# Pinscape_Pico_Expansion_Board_-_DIY_Frie.net
KiCad netlist of a schematic drawn in EAGLE
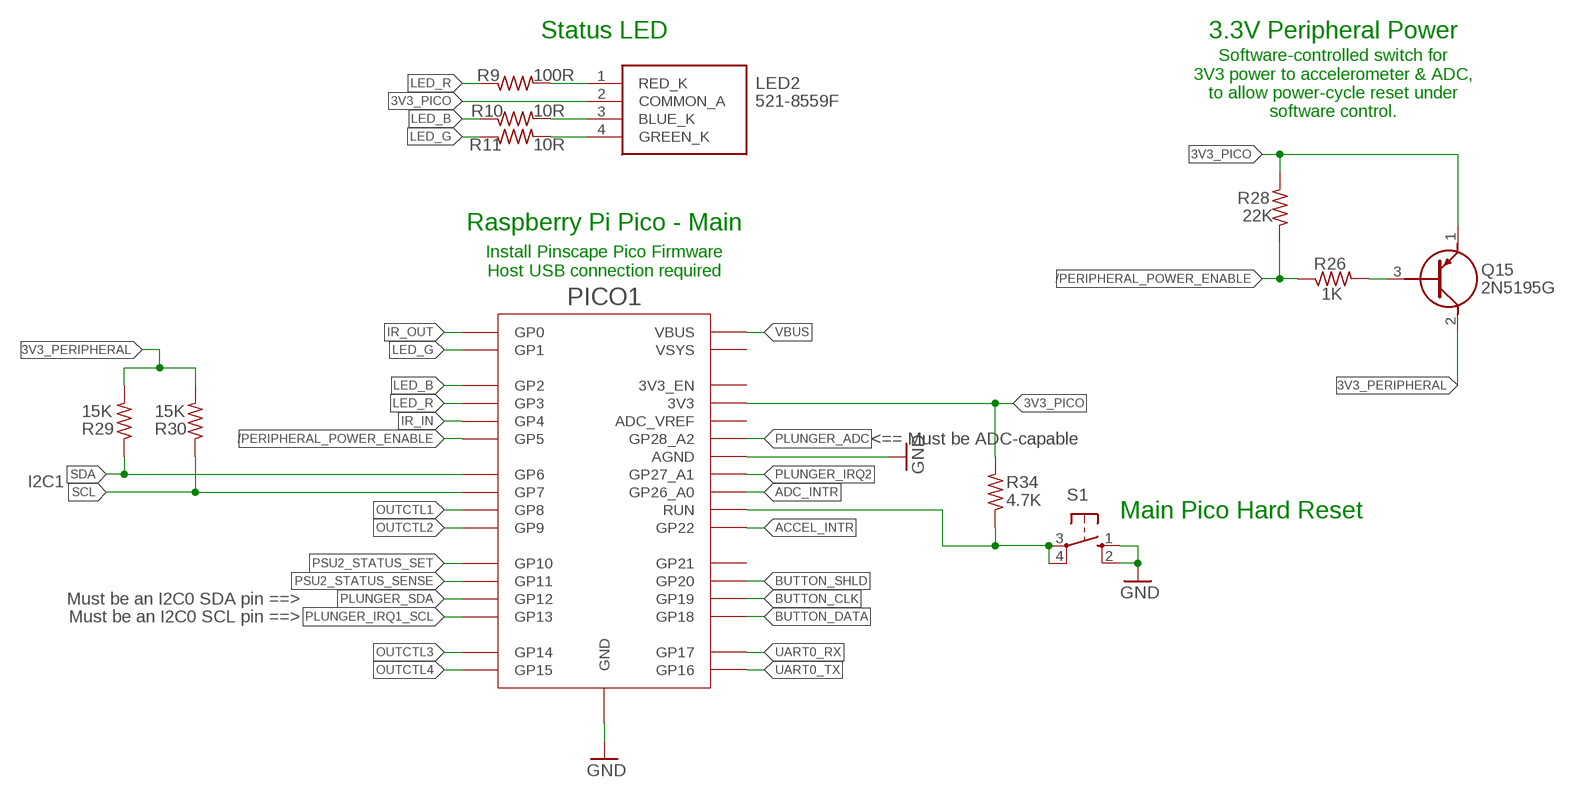
[diagram p0: schematic, sheet 1]
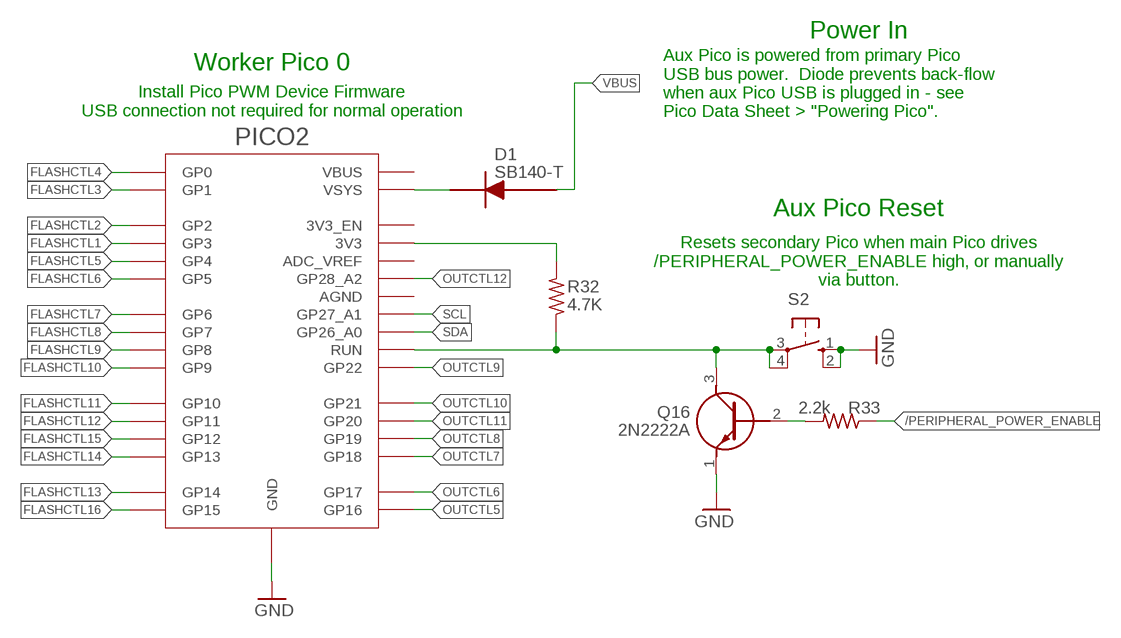
[diagram p1: schematic, sheet 2]
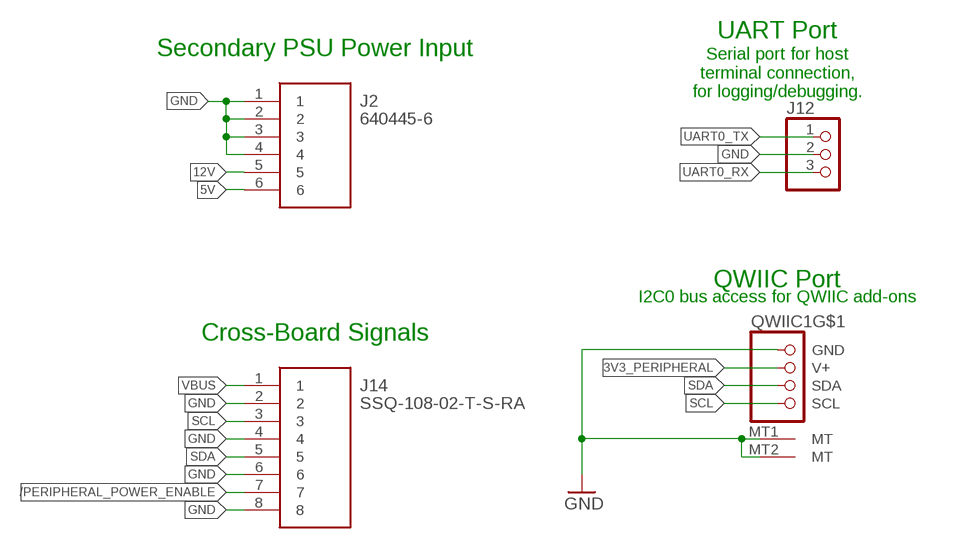
[diagram p2: schematic, sheet 3]
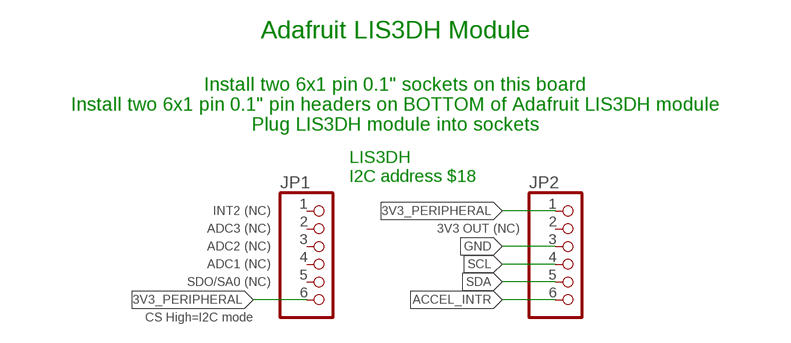
[diagram p3: schematic, sheet 4]
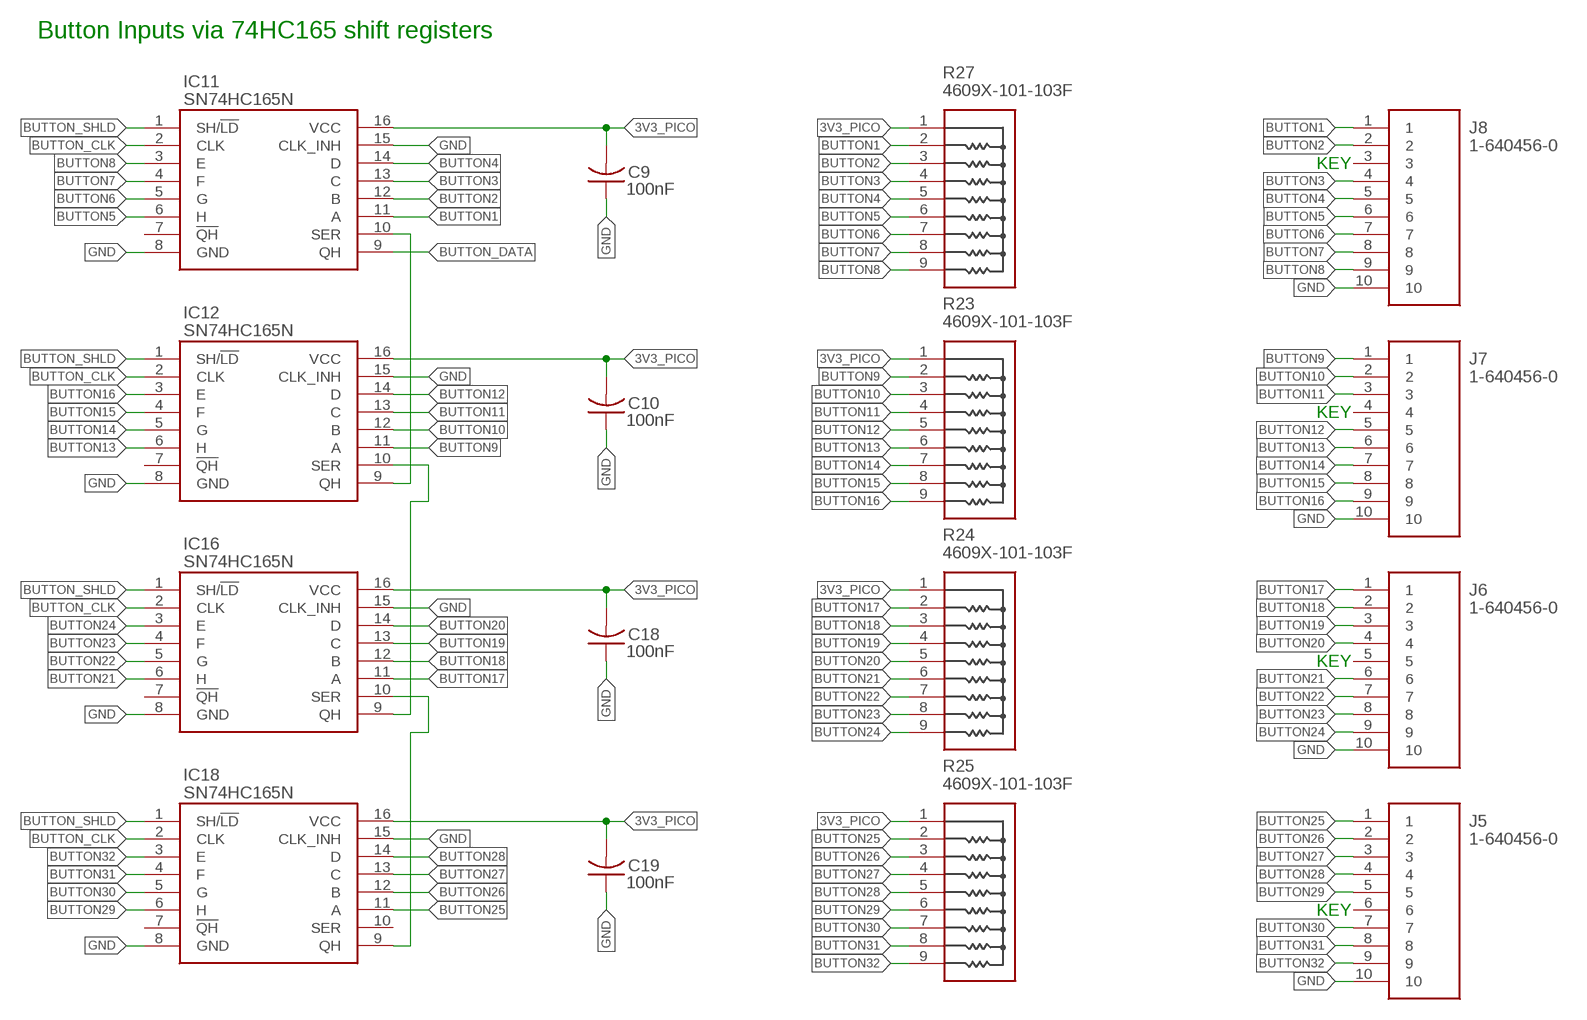
[diagram p4: schematic, sheet 5]
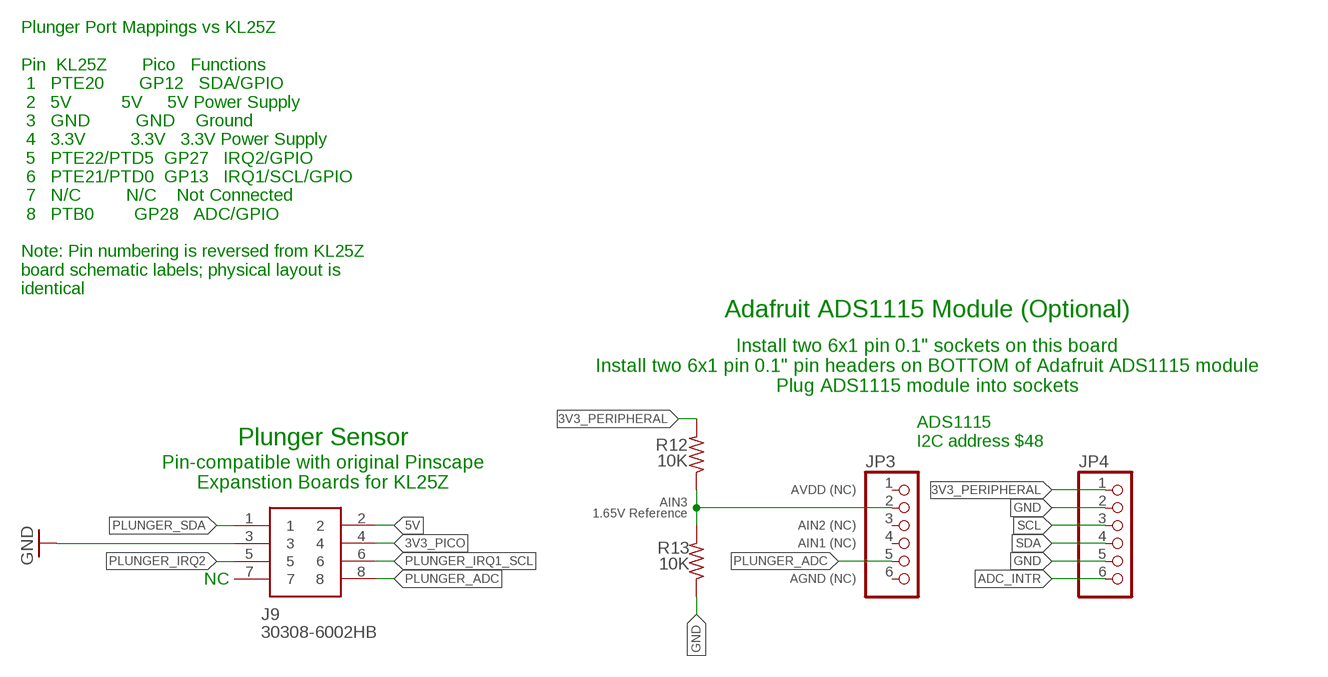
[diagram p5: schematic, sheet 6]
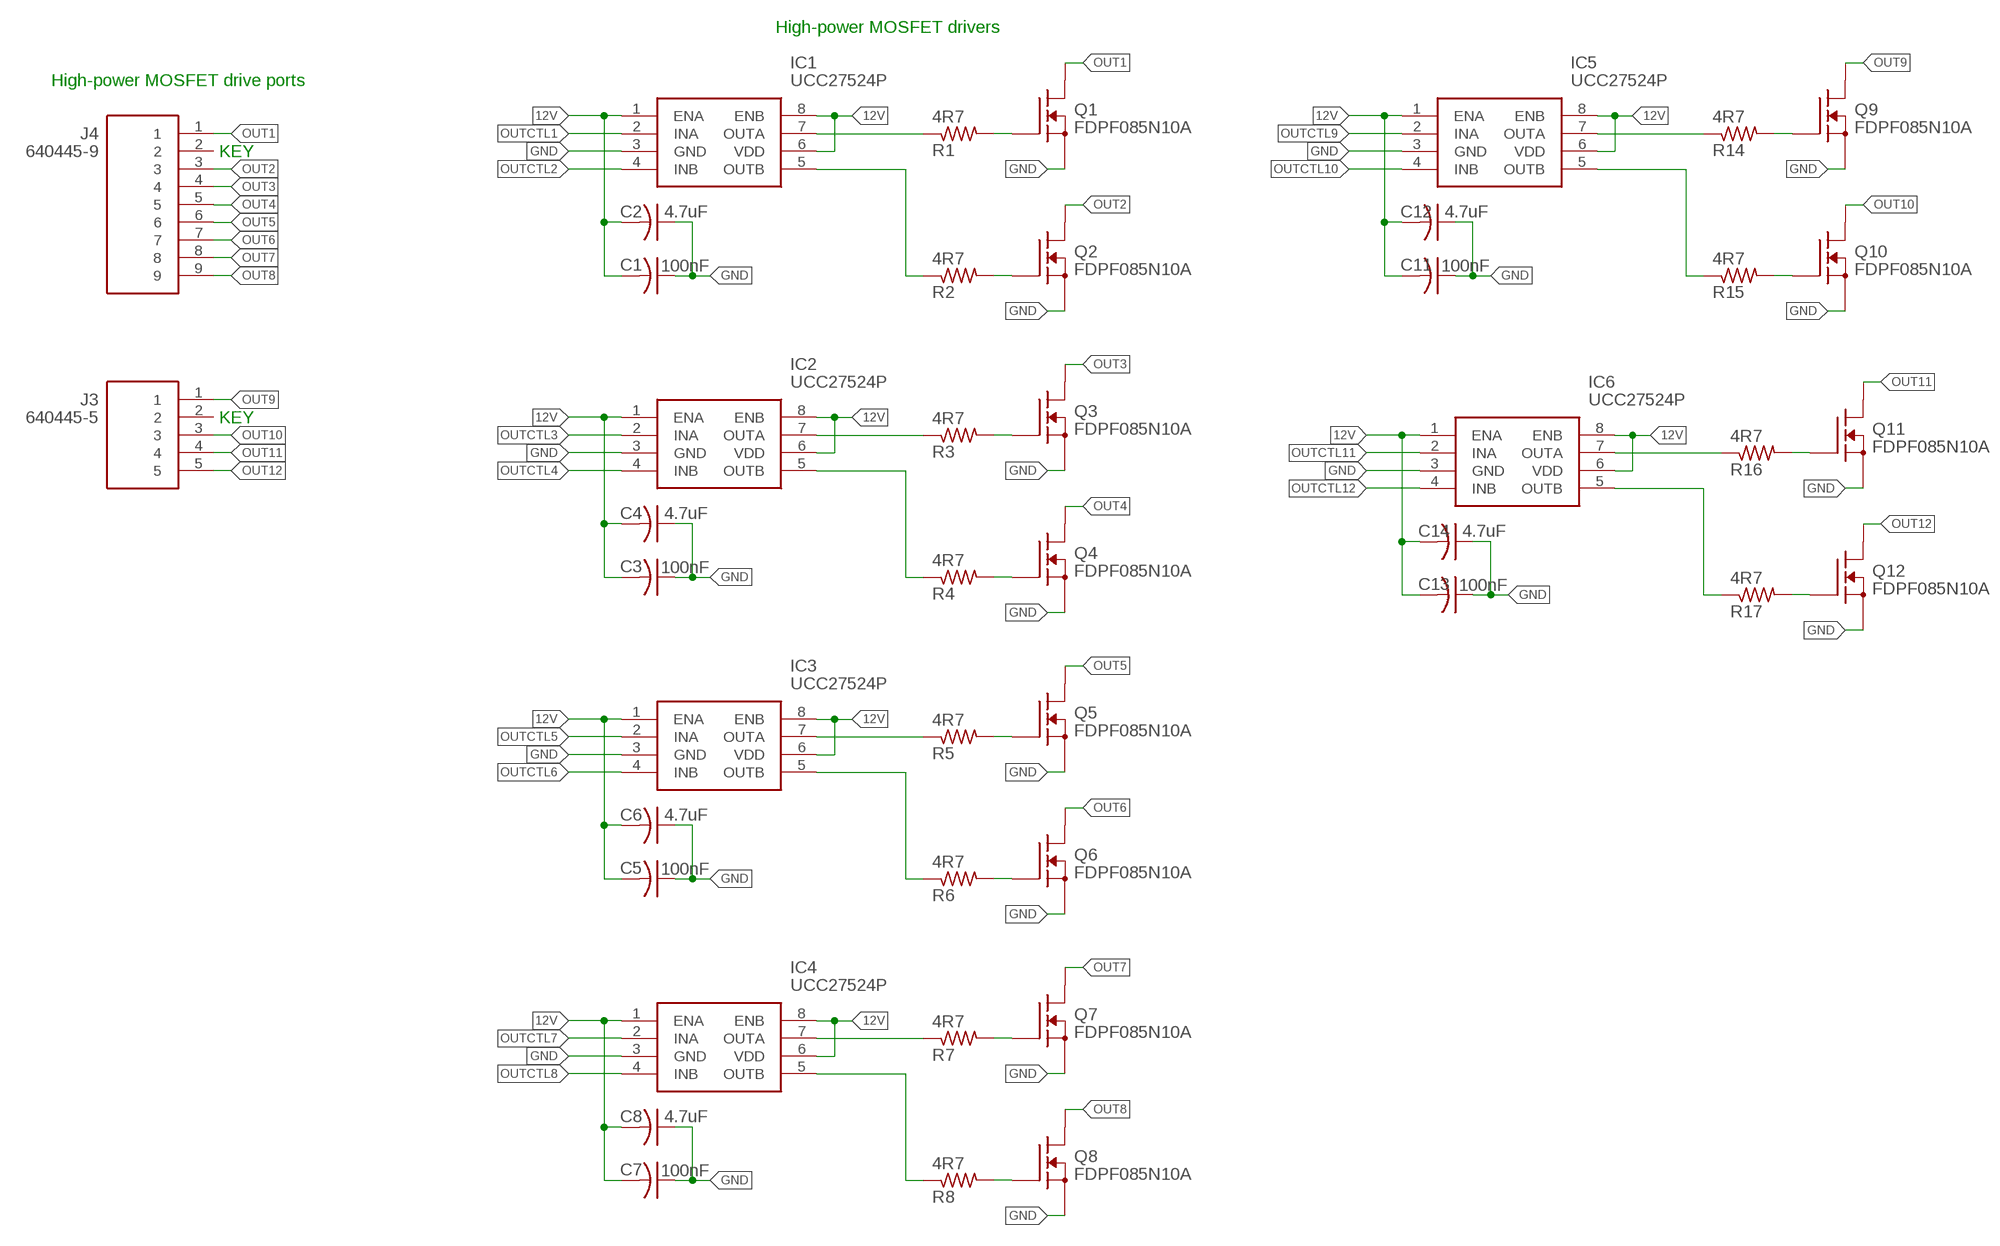
[diagram p6: schematic, sheet 7]
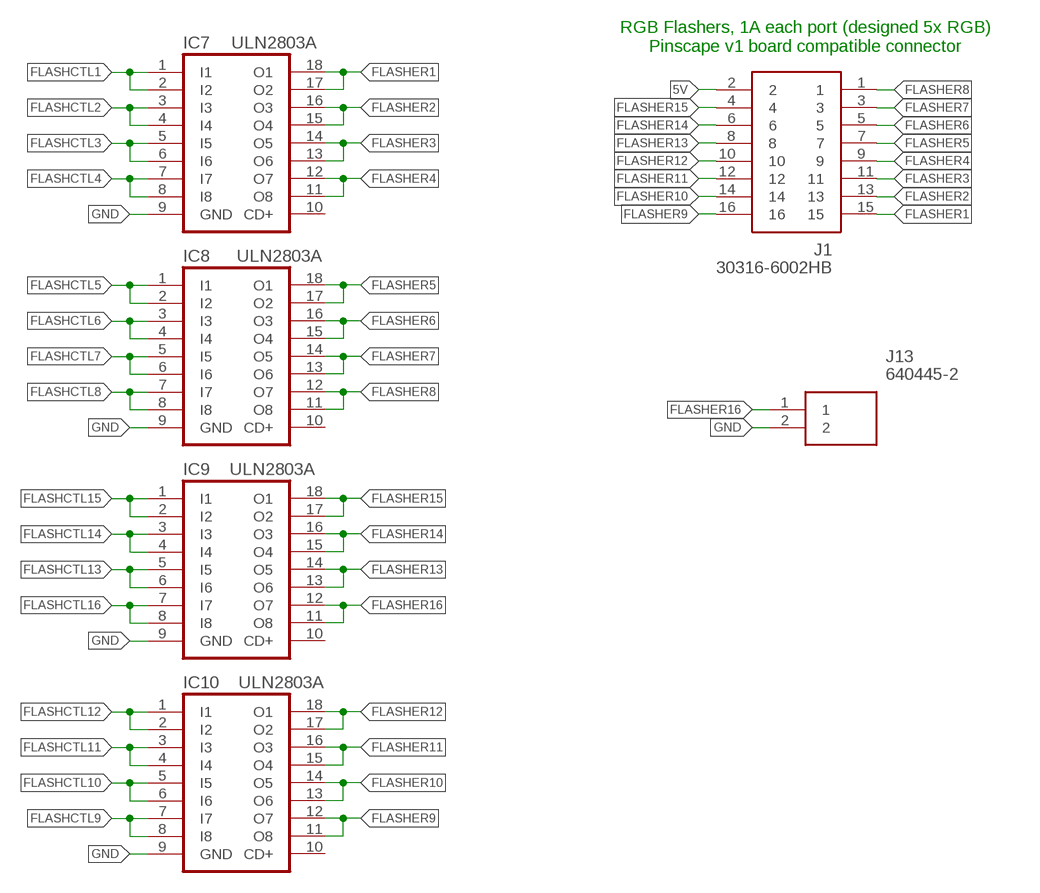
[diagram p7: schematic, sheet 8]
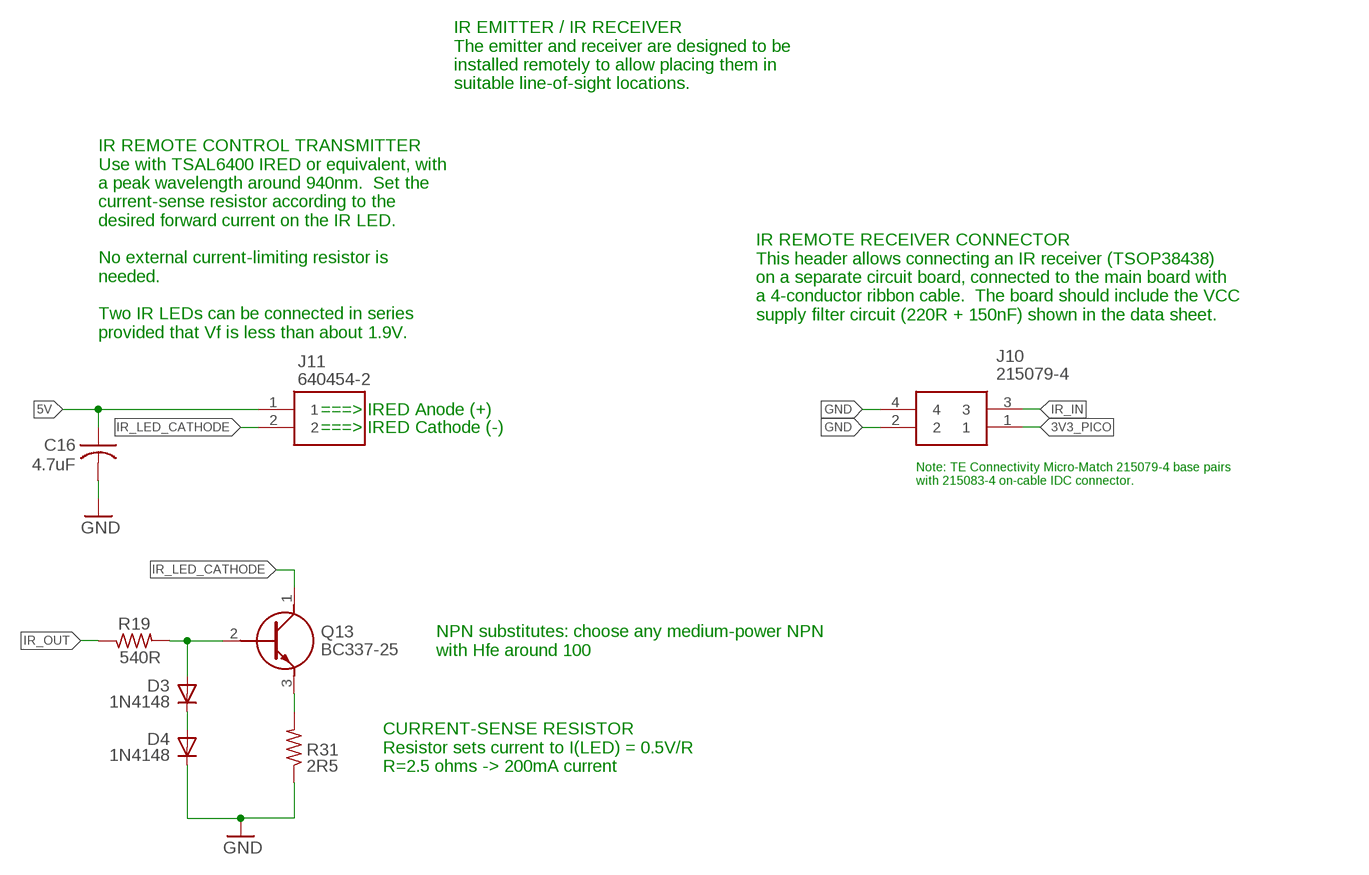
[diagram p8: schematic, sheet 9]
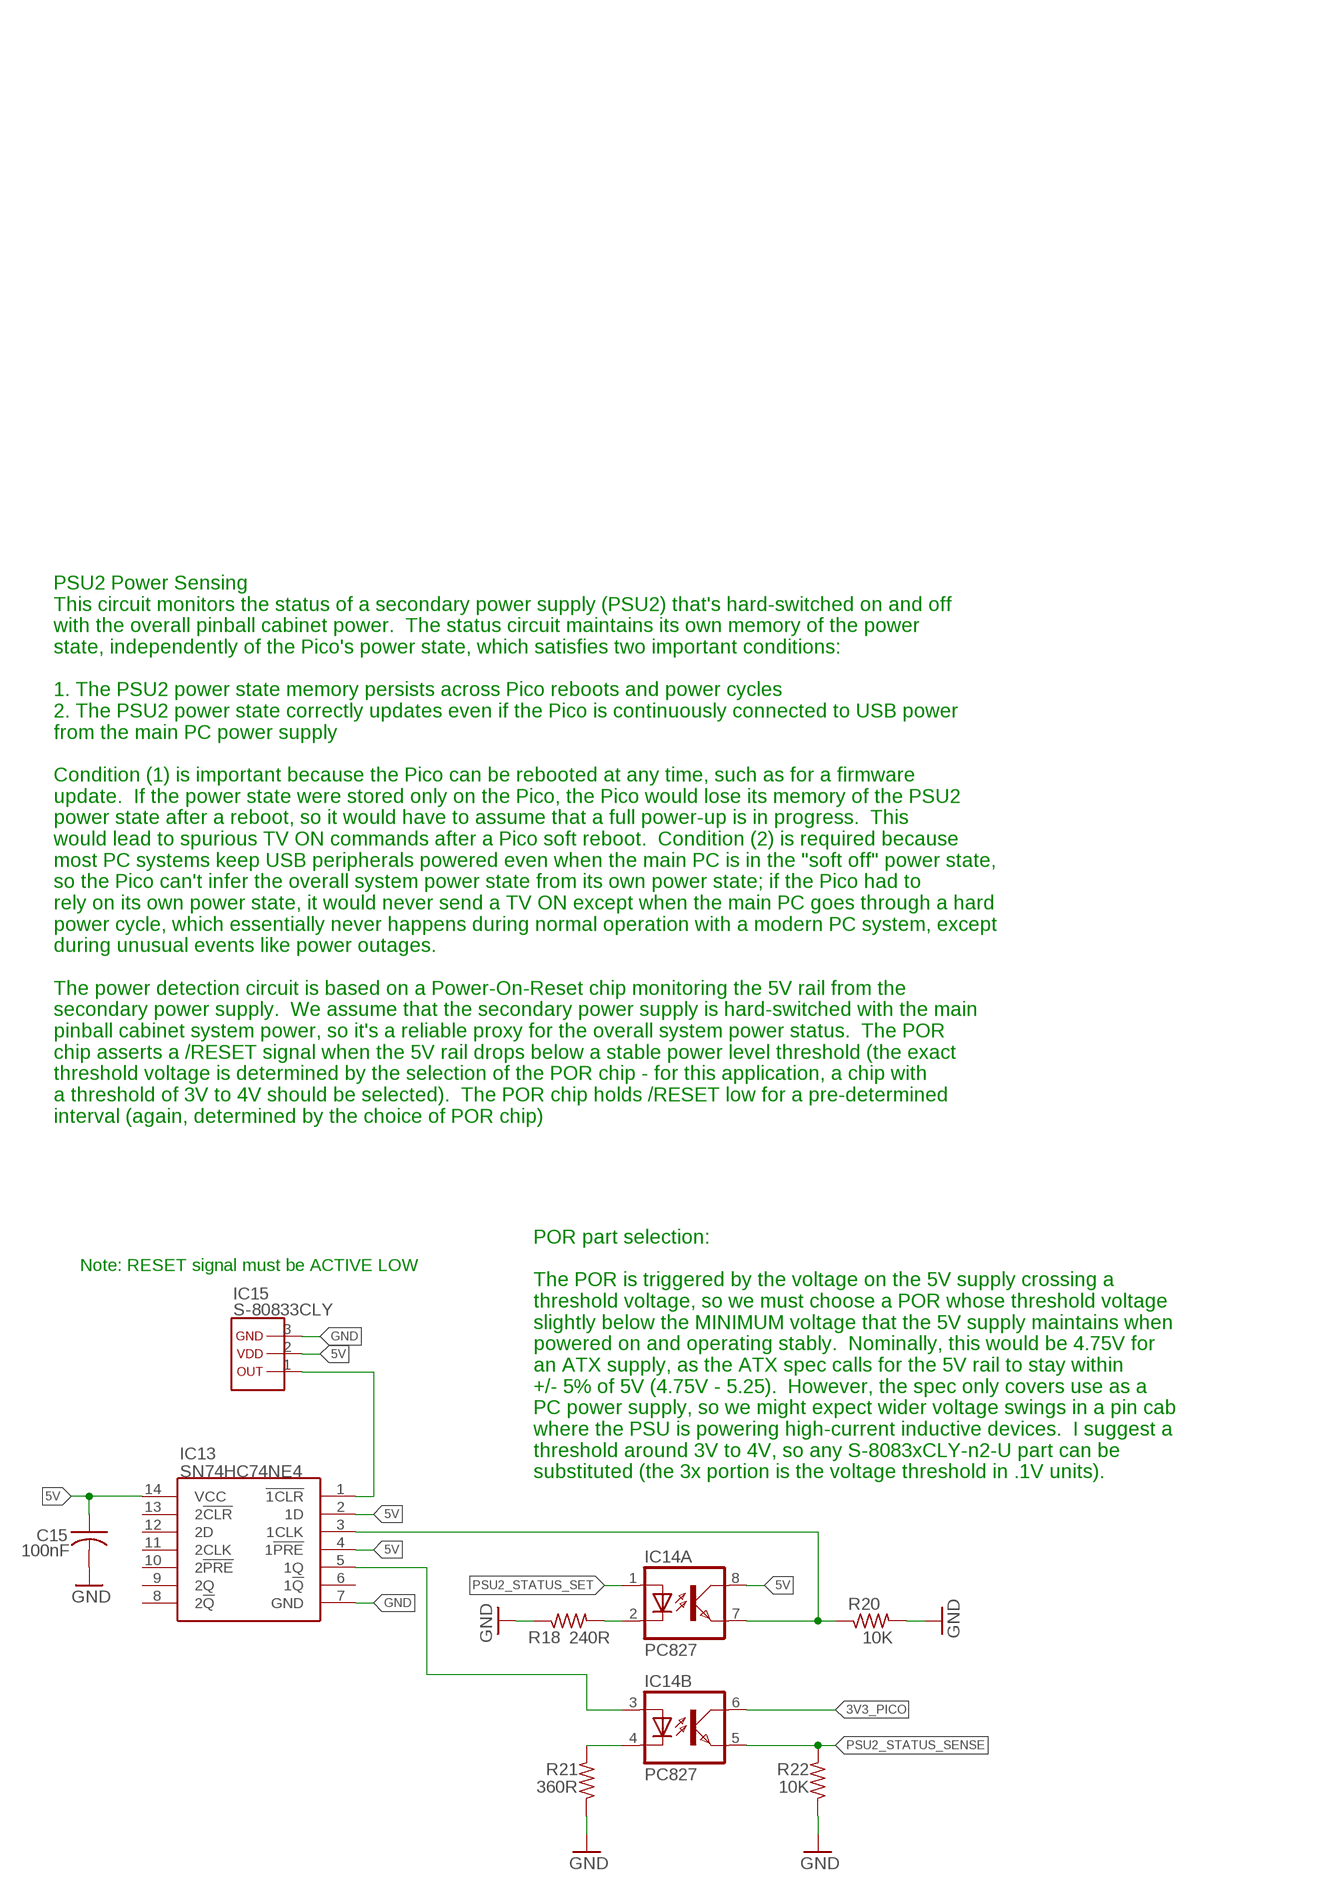
[diagram p9: schematic, sheet 10]
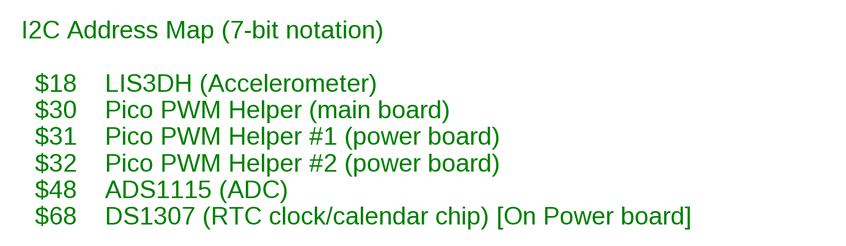
[diagram p10: schematic, sheet 11]

(export (version "E")
  (design (tool "Eeschema 10.0.6"))
  (components
    (comp (ref "C9")
      (value "100nF")
      (footprint "eagle-import:C025-024X044")
      (fields (field (name "PARTNO") "21RZ310-RC"))
      (libsource (lib "eagle-import") (part "C-US025-024X044"))
    )
    (comp (ref "C10")
      (value "100nF")
      (footprint "eagle-import:C025-024X044")
      (fields (field (name "PARTNO") "21RZ310-RC"))
      (libsource (lib "eagle-import") (part "C-US025-024X044"))
    )
    (comp (ref "C18")
      (value "100nF")
      (footprint "eagle-import:C025-024X044")
      (fields (field (name "PARTNO") "21RZ310-RC"))
      (libsource (lib "eagle-import") (part "C-US025-024X044"))
    )
    (comp (ref "C19")
      (value "100nF")
      (footprint "eagle-import:C025-024X044")
      (fields (field (name "PARTNO") "21RZ310-RC"))
      (libsource (lib "eagle-import") (part "C-US025-024X044"))
    )
    (comp (ref "IC11")
      (value "SN74HC165N")
      (footprint "eagle-import:DIP794W53P254L1930H508Q16N")
      (fields (field (name "MOUSER_PART_NUMBER") "595-SN74HC165N"))
      (libsource (lib "eagle-import") (part "SN74HC165N"))
    )
    (comp (ref "IC12")
      (value "SN74HC165N")
      (footprint "eagle-import:DIP794W53P254L1930H508Q16N")
      (fields (field (name "MOUSER_PART_NUMBER") "595-SN74HC165N"))
      (libsource (lib "eagle-import") (part "SN74HC165N"))
    )
    (comp (ref "IC16")
      (value "SN74HC165N")
      (footprint "eagle-import:DIP794W53P254L1930H508Q16N")
      (fields (field (name "MOUSER_PART_NUMBER") "595-SN74HC165N"))
      (libsource (lib "eagle-import") (part "SN74HC165N"))
    )
    (comp (ref "IC18")
      (value "SN74HC165N")
      (footprint "eagle-import:DIP794W53P254L1930H508Q16N")
      (fields (field (name "MOUSER_PART_NUMBER") "595-SN74HC165N"))
      (libsource (lib "eagle-import") (part "SN74HC165N"))
    )
    (comp (ref "J5")
      (value "1-640456-0")
      (footprint "eagle-import:SHDR10W66P0X254_1X10_2540X572X")
      (fields (field (name "MOUSER_PART_NUMBER") "571-16404560"))
      (libsource (lib "eagle-import") (part "1-640456-0"))
    )
    (comp (ref "J6")
      (value "1-640456-0")
      (footprint "eagle-import:SHDR10W66P0X254_1X10_2540X572X")
      (fields (field (name "MOUSER_PART_NUMBER") "571-16404560"))
      (libsource (lib "eagle-import") (part "1-640456-0"))
    )
    (comp (ref "J7")
      (value "1-640456-0")
      (footprint "eagle-import:SHDR10W66P0X254_1X10_2540X572X")
      (fields (field (name "MOUSER_PART_NUMBER") "571-16404560"))
      (libsource (lib "eagle-import") (part "1-640456-0"))
    )
    (comp (ref "J8")
      (value "1-640456-0")
      (footprint "eagle-import:SHDR10W66P0X254_1X10_2540X572X")
      (fields (field (name "MOUSER_PART_NUMBER") "571-16404560"))
      (libsource (lib "eagle-import") (part "1-640456-0"))
    )
    (comp (ref "R23")
      (value "4609X-101-103F")
      (footprint "eagle-import:4609X")
      (fields
        (field (name "MANUFACTURER_PART_NUMBER") "4609X-101-122LF")
        (field (name "MOUSER_PART_NUMBER") "652-4609X-1LF-1.2K")
      )
      (libsource (lib "eagle-import") (part "4609X-101-122LF"))
    )
    (comp (ref "R24")
      (value "4609X-101-103F")
      (footprint "eagle-import:4609X")
      (fields
        (field (name "MANUFACTURER_PART_NUMBER") "4609X-101-122LF")
        (field (name "MOUSER_PART_NUMBER") "652-4609X-1LF-1.2K")
      )
      (libsource (lib "eagle-import") (part "4609X-101-122LF"))
    )
    (comp (ref "R25")
      (value "4609X-101-103F")
      (footprint "eagle-import:4609X")
      (fields
        (field (name "MANUFACTURER_PART_NUMBER") "4609X-101-122LF")
        (field (name "MOUSER_PART_NUMBER") "652-4609X-1LF-1.2K")
      )
      (libsource (lib "eagle-import") (part "4609X-101-122LF"))
    )
    (comp (ref "R27")
      (value "4609X-101-103F")
      (footprint "eagle-import:4609X")
      (fields
        (field (name "MANUFACTURER_PART_NUMBER") "4609X-101-122LF")
        (field (name "MOUSER_PART_NUMBER") "652-4609X-1LF-1.2K")
      )
      (libsource (lib "eagle-import") (part "4609X-101-122LF"))
    )
    (comp (ref "JP1")
      (value "PINHD-1X6")
      (footprint "eagle-import:1X06")
      (libsource (lib "eagle-import") (part "PINHD-1X6"))
    )
    (comp (ref "JP2")
      (value "PINHD-1X6")
      (footprint "eagle-import:1X06")
      (libsource (lib "eagle-import") (part "PINHD-1X6"))
    )
    (comp (ref "J2")
      (value "640445-6")
      (footprint "eagle-import:SHDR6W183P0X396_1X6_2377X762X1")
      (fields (field (name "MOUSER_PART_NUMBER") "571-6404456"))
      (libsource (lib "eagle-import") (part "640445-6"))
    )
    (comp (ref "J12")
      (value "PINHD-1X3")
      (footprint "eagle-import:1X03")
      (libsource (lib "eagle-import") (part "PINHD-1X3"))
    )
    (comp (ref "J14")
      (value "SSQ-108-02-T-S-RA")
      (footprint "eagle-import:RHDRRA8W64P254_1X8_2083X851X24")
      (fields (field (name "MOUSER_PART_NUMBER") "200-SSQ10802TSRA"))
      (libsource (lib "eagle-import") (part "SSQ-108-02-T-S-RA"))
    )
    (comp (ref "QWIIC1")
      (value "QWIIC")
      (footprint "eagle-import:JST_SH4")
      (libsource (lib "eagle-import") (part "STEMMA_I2C_QT"))
    )
    (comp (ref "C16")
      (value "4.7uF")
      (footprint "eagle-import:C025-024X044")
      (fields (field (name "PARTNO") "810-FG14X5R1H475KRT0"))
      (libsource (lib "eagle-import") (part "C-US025-024X044"))
    )
    (comp (ref "D3")
      (value "1N4148")
      (footprint "eagle-import:DO35-7")
      (libsource (lib "eagle-import") (part "1N4148DO35-7"))
    )
    (comp (ref "D4")
      (value "1N4148")
      (footprint "eagle-import:DO35-7")
      (libsource (lib "eagle-import") (part "1N4148DO35-7"))
    )
    (comp (ref "J10")
      (value "215079-4")
      (footprint "eagle-import:2150794")
      (fields (field (name "MOUSER_PART_NUMBER") "571-215079-4"))
      (libsource (lib "eagle-import") (part "215079-4"))
    )
    (comp (ref "J11")
      (value "640454-2")
      (footprint "eagle-import:HDRV2W66P0X254_1X2_762X572X100")
      (fields (field (name "MOUSER_PART_NUMBER") "571-640454-2"))
      (libsource (lib "eagle-import") (part "640454-2"))
    )
    (comp (ref "Q13")
      (value "BC337-25")
      (footprint "eagle-import:BC33725")
      (fields (field (name "MOUSER_PART_NUMBER") "637-BC337-25"))
      (libsource (lib "eagle-import") (part "BC337-25"))
    )
    (comp (ref "R19")
      (value "540R")
      (footprint "eagle-import:0204_7")
      (fields (field (name "PARTNO") "660-MFS1/4DCT52R47R0"))
      (libsource (lib "eagle-import") (part "R-US_0204/7"))
    )
    (comp (ref "R31")
      (value "2R5")
      (footprint "eagle-import:0204_7")
      (fields (field (name "PARTNO") "660-MFS1/4DCT52R47R0"))
      (libsource (lib "eagle-import") (part "R-US_0204/7"))
    )
    (comp (ref "D1")
      (value "SB140-T")
      (footprint "eagle-import:DIOAD1408W86L464D236")
      (fields (field (name "MOUSER_PART_NUMBER") "621-SB140-T"))
      (libsource (lib "eagle-import") (part "SB140-T"))
    )
    (comp (ref "PICO2")
      (value "RPI_PICO_NO_DEBUG")
      (footprint "eagle-import:RPI_PICO_TH_NO_DEBUG")
      (libsource (lib "eagle-import") (part "RPI_PICO_NO_DEBUG"))
    )
    (comp (ref "Q16")
      (value "2N2222A")
      (footprint "eagle-import:2N2222A")
      (fields (field (name "MOUSER_PART_NUMBER") "637-2N2222A"))
      (libsource (lib "eagle-import") (part "2N2222A"))
    )
    (comp (ref "R32")
      (value "4.7K")
      (footprint "eagle-import:0204_7")
      (fields (field (name "PARTNO") "660-MFS1/4DCT52R47R0"))
      (libsource (lib "eagle-import") (part "R-US_0204/7"))
    )
    (comp (ref "R33")
      (value "2.2k")
      (footprint "eagle-import:0204_7")
      (fields (field (name "PARTNO") "660-MFS1/4DCT52R47R0"))
      (libsource (lib "eagle-import") (part "R-US_0204/7"))
    )
    (comp (ref "S2")
      (value "10-XX")
      (footprint "eagle-import:B3F-10XX")
      (fields (field (name "MPN") "B3F-1000"))
      (libsource (lib "eagle-import") (part "10-XX"))
    )
    (comp (ref "C15")
      (value "100nF")
      (footprint "eagle-import:C025-024X044")
      (fields (field (name "PARTNO") "21RZ310-RC"))
      (libsource (lib "eagle-import") (part "C-US025-024X044"))
    )
    (comp (ref "IC13")
      (value "SN74HC74NE4")
      (footprint "eagle-import:DIP794W53P254L1930H508Q14N")
      (fields (field (name "MOUSER_PART_NUMBER") "595-SN74HC74NE4"))
      (libsource (lib "eagle-import") (part "SN74HC74NE4"))
    )
    (comp (ref "IC14")
      (value "PC827")
      (footprint "eagle-import:DIL08")
      (libsource (lib "eagle-import") (part "PC827"))
    )
    (comp (ref "IC15")
      (value "S-80833CLY")
      (footprint "eagle-import:TO-92_(TO-226)")
      (libsource (lib "eagle-import") (part "S-80833CLY-B2-UTO92"))
    )
    (comp (ref "R18")
      (value "240R")
      (footprint "eagle-import:0204_7")
      (fields (field (name "PARTNO") "660-MFS1/4DCT52R47R0"))
      (libsource (lib "eagle-import") (part "R-US_0204/7"))
    )
    (comp (ref "R20")
      (value "10K")
      (footprint "eagle-import:0204_7")
      (fields (field (name "PARTNO") "660-MFS1/4DCT52R47R0"))
      (libsource (lib "eagle-import") (part "R-US_0204/7"))
    )
    (comp (ref "R21")
      (value "360R")
      (footprint "eagle-import:0204_7")
      (fields (field (name "PARTNO") "660-MFS1/4DCT52R47R0"))
      (libsource (lib "eagle-import") (part "R-US_0204/7"))
    )
    (comp (ref "R22")
      (value "10K")
      (footprint "eagle-import:0204_7")
      (fields (field (name "PARTNO") "660-MFS1/4DCT52R47R0"))
      (libsource (lib "eagle-import") (part "R-US_0204/7"))
    )
    (comp (ref "LED2")
      (value "521-8559F")
      (footprint "eagle-import:5218559F")
      (fields (field (name "MOUSER_PART_NUMBER") "645-5218559F"))
      (libsource (lib "eagle-import") (part "521-8559F"))
    )
    (comp (ref "PICO1")
      (value "RPI_PICO_NO_DEBUG")
      (footprint "eagle-import:RPI_PICO_TH_NO_DEBUG")
      (libsource (lib "eagle-import") (part "RPI_PICO_NO_DEBUG"))
    )
    (comp (ref "Q15")
      (value "2N5195G")
      (footprint "eagle-import:TO229P300X760X1364-3P")
      (fields (field (name "MOUSER_PART_NUMBER") "863-2N5195G"))
      (libsource (lib "eagle-import") (part "2N5195G"))
    )
    (comp (ref "R9")
      (value "100R")
      (footprint "eagle-import:0204_7")
      (fields (field (name "PARTNO") "660-MFS1/4DCT52R47R0"))
      (libsource (lib "eagle-import") (part "R-US_0204/7"))
    )
    (comp (ref "R10")
      (value "10R")
      (footprint "eagle-import:0204_7")
      (fields (field (name "PARTNO") "660-MFS1/4DCT52R47R0"))
      (libsource (lib "eagle-import") (part "R-US_0204/7"))
    )
    (comp (ref "R11")
      (value "10R")
      (footprint "eagle-import:0204_7")
      (fields (field (name "PARTNO") "660-MFS1/4DCT52R47R0"))
      (libsource (lib "eagle-import") (part "R-US_0204/7"))
    )
    (comp (ref "R26")
      (value "1K")
      (footprint "eagle-import:0204_7")
      (fields (field (name "PARTNO") "660-MFS1/4DCT52R47R0"))
      (libsource (lib "eagle-import") (part "R-US_0204/7"))
    )
    (comp (ref "R28")
      (value "22K")
      (footprint "eagle-import:0204_7")
      (fields (field (name "PARTNO") "660-MFS1/4DCT52R47R0"))
      (libsource (lib "eagle-import") (part "R-US_0204/7"))
    )
    (comp (ref "R29")
      (value "15K")
      (footprint "eagle-import:0204_7")
      (fields (field (name "PARTNO") "660-MFS1/4DCT52R47R0"))
      (libsource (lib "eagle-import") (part "R-US_0204/7"))
    )
    (comp (ref "R30")
      (value "15K")
      (footprint "eagle-import:0204_7")
      (fields (field (name "PARTNO") "660-MFS1/4DCT52R47R0"))
      (libsource (lib "eagle-import") (part "R-US_0204/7"))
    )
    (comp (ref "R34")
      (value "4.7K")
      (footprint "eagle-import:0204_7")
      (fields (field (name "PARTNO") "660-MFS1/4DCT52R47R0"))
      (libsource (lib "eagle-import") (part "R-US_0204/7"))
    )
    (comp (ref "S1")
      (value "10-XX")
      (footprint "eagle-import:B3F-10XX")
      (fields (field (name "MPN") "B3F-1000"))
      (libsource (lib "eagle-import") (part "10-XX"))
    )
    (comp (ref "IC7")
      (value "ULN2803A")
      (footprint "eagle-import:DIL18")
      (libsource (lib "eagle-import") (part "ULN2803A"))
    )
    (comp (ref "IC8")
      (value "ULN2803A")
      (footprint "eagle-import:DIL18")
      (libsource (lib "eagle-import") (part "ULN2803A"))
    )
    (comp (ref "IC9")
      (value "ULN2803A")
      (footprint "eagle-import:DIL18")
      (libsource (lib "eagle-import") (part "ULN2803A"))
    )
    (comp (ref "IC10")
      (value "ULN2803A")
      (footprint "eagle-import:DIL18")
      (libsource (lib "eagle-import") (part "ULN2803A"))
    )
    (comp (ref "J1")
      (value "30316-6002HB")
      (footprint "eagle-import:3M-30316-6002HB")
      (fields (field (name "MOUSER_PART_NUMBER") "517-30316-6002"))
      (libsource (lib "eagle-import") (part "30316-6002HB"))
    )
    (comp (ref "J13")
      (value "640445-2")
      (footprint "eagle-import:SHDR2W117P0X396_1X2_792X762X11")
      (fields (field (name "MOUSER_PART_NUMBER") "5716404452"))
      (libsource (lib "eagle-import") (part "640445-2"))
    )
    (comp (ref "J9")
      (value "30308-6002HB")
      (footprint "eagle-import:SHDR8W69P254_2X4_1780X878X955P")
      (libsource (lib "eagle-import") (part "30308-6002HB"))
    )
    (comp (ref "JP3")
      (value "PINHD-1X6")
      (footprint "eagle-import:1X06")
      (libsource (lib "eagle-import") (part "PINHD-1X6"))
    )
    (comp (ref "JP4")
      (value "PINHD-1X6")
      (footprint "eagle-import:1X06")
      (libsource (lib "eagle-import") (part "PINHD-1X6"))
    )
    (comp (ref "R12")
      (value "10K")
      (footprint "eagle-import:0204_7")
      (fields (field (name "PARTNO") "660-MFS1/4DCT52R47R0"))
      (libsource (lib "eagle-import") (part "R-US_0204/7"))
    )
    (comp (ref "R13")
      (value "10K")
      (footprint "eagle-import:0204_7")
      (fields (field (name "PARTNO") "660-MFS1/4DCT52R47R0"))
      (libsource (lib "eagle-import") (part "R-US_0204/7"))
    )
    (comp (ref "C1")
      (value "100nF")
      (footprint "eagle-import:C025-024X044")
      (fields (field (name "PARTNO") "21RZ310-RC"))
      (libsource (lib "eagle-import") (part "C-US025-024X044"))
    )
    (comp (ref "C2")
      (value "4.7uF")
      (footprint "eagle-import:C025-024X044")
      (fields (field (name "PARTNO") "810-FG14X5R1H475KRT0"))
      (libsource (lib "eagle-import") (part "C-US025-024X044"))
    )
    (comp (ref "C3")
      (value "100nF")
      (footprint "eagle-import:C025-024X044")
      (fields (field (name "PARTNO") "21RZ310-RC"))
      (libsource (lib "eagle-import") (part "C-US025-024X044"))
    )
    (comp (ref "C4")
      (value "4.7uF")
      (footprint "eagle-import:C025-024X044")
      (fields (field (name "PARTNO") "810-FG14X5R1H475KRT0"))
      (libsource (lib "eagle-import") (part "C-US025-024X044"))
    )
    (comp (ref "C5")
      (value "100nF")
      (footprint "eagle-import:C025-024X044")
      (fields (field (name "PARTNO") "21RZ310-RC"))
      (libsource (lib "eagle-import") (part "C-US025-024X044"))
    )
    (comp (ref "C6")
      (value "4.7uF")
      (footprint "eagle-import:C025-024X044")
      (fields (field (name "PARTNO") "810-FG14X5R1H475KRT0"))
      (libsource (lib "eagle-import") (part "C-US025-024X044"))
    )
    (comp (ref "C7")
      (value "100nF")
      (footprint "eagle-import:C025-024X044")
      (fields (field (name "PARTNO") "21RZ310-RC"))
      (libsource (lib "eagle-import") (part "C-US025-024X044"))
    )
    (comp (ref "C8")
      (value "4.7uF")
      (footprint "eagle-import:C025-024X044")
      (fields (field (name "PARTNO") "810-FG14X5R1H475KRT0"))
      (libsource (lib "eagle-import") (part "C-US025-024X044"))
    )
    (comp (ref "C11")
      (value "100nF")
      (footprint "eagle-import:C025-024X044")
      (fields (field (name "PARTNO") "21RZ310-RC"))
      (libsource (lib "eagle-import") (part "C-US025-024X044"))
    )
    (comp (ref "C12")
      (value "4.7uF")
      (footprint "eagle-import:C025-024X044")
      (fields (field (name "PARTNO") "810-FG14X5R1H475KRT0"))
      (libsource (lib "eagle-import") (part "C-US025-024X044"))
    )
    (comp (ref "C13")
      (value "100nF")
      (footprint "eagle-import:C025-024X044")
      (fields (field (name "PARTNO") "21RZ310-RC"))
      (libsource (lib "eagle-import") (part "C-US025-024X044"))
    )
    (comp (ref "C14")
      (value "4.7uF")
      (footprint "eagle-import:C025-024X044")
      (fields (field (name "PARTNO") "810-FG14X5R1H475KRT0"))
      (libsource (lib "eagle-import") (part "C-US025-024X044"))
    )
    (comp (ref "IC1")
      (value "UCC27524P")
      (footprint "eagle-import:DIP794W53P254L959H508Q8N")
      (fields (field (name "MOUSER_PART_NUMBER") "595-UCC27524P"))
      (libsource (lib "eagle-import") (part "UCC27524P"))
    )
    (comp (ref "IC2")
      (value "UCC27524P")
      (footprint "eagle-import:DIP794W53P254L959H508Q8N")
      (fields (field (name "MOUSER_PART_NUMBER") "595-UCC27524P"))
      (libsource (lib "eagle-import") (part "UCC27524P"))
    )
    (comp (ref "IC3")
      (value "UCC27524P")
      (footprint "eagle-import:DIP794W53P254L959H508Q8N")
      (fields (field (name "MOUSER_PART_NUMBER") "595-UCC27524P"))
      (libsource (lib "eagle-import") (part "UCC27524P"))
    )
    (comp (ref "IC4")
      (value "UCC27524P")
      (footprint "eagle-import:DIP794W53P254L959H508Q8N")
      (fields (field (name "MOUSER_PART_NUMBER") "595-UCC27524P"))
      (libsource (lib "eagle-import") (part "UCC27524P"))
    )
    (comp (ref "IC5")
      (value "UCC27524P")
      (footprint "eagle-import:DIP794W53P254L959H508Q8N")
      (fields (field (name "MOUSER_PART_NUMBER") "595-UCC27524P"))
      (libsource (lib "eagle-import") (part "UCC27524P"))
    )
    (comp (ref "IC6")
      (value "UCC27524P")
      (footprint "eagle-import:DIP794W53P254L959H508Q8N")
      (fields (field (name "MOUSER_PART_NUMBER") "595-UCC27524P"))
      (libsource (lib "eagle-import") (part "UCC27524P"))
    )
    (comp (ref "J3")
      (value "640445-5")
      (footprint "eagle-import:HDRV5W117P0X396_1X5_1981X762X1")
      (fields (field (name "MOUSER_PART_NUMBER") "571-640445-5"))
      (libsource (lib "eagle-import") (part "640445-5"))
    )
    (comp (ref "J4")
      (value "640445-9")
      (footprint "eagle-import:SHDR9W117P0X396_1X9_3566X762X1")
      (fields (field (name "MOUSER_PART_NUMBER") "571-6404459"))
      (libsource (lib "eagle-import") (part "640445-9"))
    )
    (comp (ref "Q1")
      (value "FDPF085N10A")
      (footprint "eagle-import:TO220BV")
      (fields (field (name "PARTNO") "FDPF085N10A"))
      (libsource (lib "eagle-import") (part "BUK7575-55A"))
    )
    (comp (ref "Q2")
      (value "FDPF085N10A")
      (footprint "eagle-import:TO220BV")
      (fields (field (name "PARTNO") "FDPF085N10A"))
      (libsource (lib "eagle-import") (part "BUK7575-55A"))
    )
    (comp (ref "Q3")
      (value "FDPF085N10A")
      (footprint "eagle-import:TO220BV")
      (fields (field (name "PARTNO") "FDPF085N10A"))
      (libsource (lib "eagle-import") (part "BUK7575-55A"))
    )
    (comp (ref "Q4")
      (value "FDPF085N10A")
      (footprint "eagle-import:TO220BV")
      (fields (field (name "PARTNO") "FDPF085N10A"))
      (libsource (lib "eagle-import") (part "BUK7575-55A"))
    )
    (comp (ref "Q5")
      (value "FDPF085N10A")
      (footprint "eagle-import:TO220BV")
      (fields (field (name "PARTNO") "FDPF085N10A"))
      (libsource (lib "eagle-import") (part "BUK7575-55A"))
    )
    (comp (ref "Q6")
      (value "FDPF085N10A")
      (footprint "eagle-import:TO220BV")
      (fields (field (name "PARTNO") "FDPF085N10A"))
      (libsource (lib "eagle-import") (part "BUK7575-55A"))
    )
    (comp (ref "Q7")
      (value "FDPF085N10A")
      (footprint "eagle-import:TO220BV")
      (fields (field (name "PARTNO") "FDPF085N10A"))
      (libsource (lib "eagle-import") (part "BUK7575-55A"))
    )
    (comp (ref "Q8")
      (value "FDPF085N10A")
      (footprint "eagle-import:TO220BV")
      (fields (field (name "PARTNO") "FDPF085N10A"))
      (libsource (lib "eagle-import") (part "BUK7575-55A"))
    )
    (comp (ref "Q9")
      (value "FDPF085N10A")
      (footprint "eagle-import:TO220BV")
      (fields (field (name "PARTNO") "FDPF085N10A"))
      (libsource (lib "eagle-import") (part "BUK7575-55A"))
    )
    (comp (ref "Q10")
      (value "FDPF085N10A")
      (footprint "eagle-import:TO220BV")
      (fields (field (name "PARTNO") "FDPF085N10A"))
      (libsource (lib "eagle-import") (part "BUK7575-55A"))
    )
    (comp (ref "Q11")
      (value "FDPF085N10A")
      (footprint "eagle-import:TO220BV")
      (fields (field (name "PARTNO") "FDPF085N10A"))
      (libsource (lib "eagle-import") (part "BUK7575-55A"))
    )
    (comp (ref "Q12")
      (value "FDPF085N10A")
      (footprint "eagle-import:TO220BV")
      (fields (field (name "PARTNO") "FDPF085N10A"))
      (libsource (lib "eagle-import") (part "BUK7575-55A"))
    )
    (comp (ref "R1")
      (value "4R7")
      (footprint "eagle-import:0204_5")
      (fields (field (name "PARTNO") "660-MFS1/4DCT52R47R0"))
      (libsource (lib "eagle-import") (part "R-US_0204/5"))
    )
    (comp (ref "R2")
      (value "4R7")
      (footprint "eagle-import:0204_5")
      (fields (field (name "PARTNO") "660-MFS1/4DCT52R47R0"))
      (libsource (lib "eagle-import") (part "R-US_0204/5"))
    )
    (comp (ref "R3")
      (value "4R7")
      (footprint "eagle-import:0204_5")
      (fields (field (name "PARTNO") "660-MFS1/4DCT52R47R0"))
      (libsource (lib "eagle-import") (part "R-US_0204/5"))
    )
    (comp (ref "R4")
      (value "4R7")
      (footprint "eagle-import:0204_5")
      (fields (field (name "PARTNO") "660-MFS1/4DCT52R47R0"))
      (libsource (lib "eagle-import") (part "R-US_0204/5"))
    )
    (comp (ref "R5")
      (value "4R7")
      (footprint "eagle-import:0204_5")
      (fields (field (name "PARTNO") "660-MFS1/4DCT52R47R0"))
      (libsource (lib "eagle-import") (part "R-US_0204/5"))
    )
    (comp (ref "R6")
      (value "4R7")
      (footprint "eagle-import:0204_5")
      (fields (field (name "PARTNO") "660-MFS1/4DCT52R47R0"))
      (libsource (lib "eagle-import") (part "R-US_0204/5"))
    )
    (comp (ref "R7")
      (value "4R7")
      (footprint "eagle-import:0204_5")
      (fields (field (name "PARTNO") "660-MFS1/4DCT52R47R0"))
      (libsource (lib "eagle-import") (part "R-US_0204/5"))
    )
    (comp (ref "R8")
      (value "4R7")
      (footprint "eagle-import:0204_5")
      (fields (field (name "PARTNO") "660-MFS1/4DCT52R47R0"))
      (libsource (lib "eagle-import") (part "R-US_0204/5"))
    )
    (comp (ref "R14")
      (value "4R7")
      (footprint "eagle-import:0204_5")
      (fields (field (name "PARTNO") "660-MFS1/4DCT52R47R0"))
      (libsource (lib "eagle-import") (part "R-US_0204/5"))
    )
    (comp (ref "R15")
      (value "4R7")
      (footprint "eagle-import:0204_5")
      (fields (field (name "PARTNO") "660-MFS1/4DCT52R47R0"))
      (libsource (lib "eagle-import") (part "R-US_0204/5"))
    )
    (comp (ref "R16")
      (value "4R7")
      (footprint "eagle-import:0204_5")
      (fields (field (name "PARTNO") "660-MFS1/4DCT52R47R0"))
      (libsource (lib "eagle-import") (part "R-US_0204/5"))
    )
    (comp (ref "R17")
      (value "4R7")
      (footprint "eagle-import:0204_5")
      (fields (field (name "PARTNO") "660-MFS1/4DCT52R47R0"))
      (libsource (lib "eagle-import") (part "R-US_0204/5"))
    )
  )
  (nets
    (net (code "1") (name "3V3_PERIPHERAL") (class "Default")
      (node (ref "JP1") (pin "6") (pinfunction "6_6") (pintype "passive"))
      (node (ref "JP2") (pin "1") (pinfunction "1_1") (pintype "passive"))
      (node (ref "JP4") (pin "1") (pinfunction "1_1") (pintype "passive"))
      (node (ref "Q15") (pin "2") (pinfunction "C_2") (pintype "bidirectional"))
      (node (ref "QWIIC1") (pin "2") (pinfunction "V+_2") (pintype "passive"))
      (node (ref "R12") (pin "2") (pinfunction "2_2") (pintype "passive"))
      (node (ref "R29") (pin "2") (pinfunction "2_2") (pintype "passive"))
      (node (ref "R30") (pin "2") (pinfunction "2_2") (pintype "passive"))
    )
    (net (code "2") (name "3V3_PICO") (class "Default")
      (node (ref "C10") (pin "2") (pinfunction "2_2") (pintype "passive"))
      (node (ref "C18") (pin "2") (pinfunction "2_2") (pintype "passive"))
      (node (ref "C19") (pin "2") (pinfunction "2_2") (pintype "passive"))
      (node (ref "C9") (pin "2") (pinfunction "2_2") (pintype "passive"))
      (node (ref "IC11") (pin "16") (pinfunction "VCC_16") (pintype "bidirectional"))
      (node (ref "IC12") (pin "16") (pinfunction "VCC_16") (pintype "bidirectional"))
      (node (ref "IC14") (pin "6") (pinfunction "COL_6") (pintype "passive"))
      (node (ref "IC16") (pin "16") (pinfunction "VCC_16") (pintype "bidirectional"))
      (node (ref "IC18") (pin "16") (pinfunction "VCC_16") (pintype "bidirectional"))
      (node (ref "J10") (pin "1") (pinfunction "1_1") (pintype "bidirectional"))
      (node (ref "J9") (pin "4") (pinfunction "4_4") (pintype "bidirectional"))
      (node (ref "LED2") (pin "2") (pinfunction "COMMON_A_2") (pintype "bidirectional"))
      (node (ref "PICO1") (pin "3V3") (pinfunction "3V3_3V3") (pintype "bidirectional"))
      (node (ref "Q15") (pin "1") (pinfunction "E_1") (pintype "bidirectional"))
      (node (ref "R23") (pin "1") (pinfunction "1_1") (pintype "bidirectional"))
      (node (ref "R24") (pin "1") (pinfunction "1_1") (pintype "bidirectional"))
      (node (ref "R25") (pin "1") (pinfunction "1_1") (pintype "bidirectional"))
      (node (ref "R27") (pin "1") (pinfunction "1_1") (pintype "bidirectional"))
      (node (ref "R28") (pin "2") (pinfunction "2_2") (pintype "passive"))
      (node (ref "R34") (pin "2") (pinfunction "2_2") (pintype "passive"))
    )
    (net (code "3") (name "5V") (class "Default")
      (node (ref "C15") (pin "1") (pinfunction "1_1") (pintype "passive"))
      (node (ref "C16") (pin "1") (pinfunction "1_1") (pintype "passive"))
      (node (ref "IC13") (pin "14") (pinfunction "VCC_14") (pintype "bidirectional"))
      (node (ref "IC13") (pin "2") (pinfunction "1D_2") (pintype "bidirectional"))
      (node (ref "IC13") (pin "4") (pinfunction "1~{PRE}_4") (pintype "bidirectional"))
      (node (ref "IC14") (pin "8") (pinfunction "COL_8") (pintype "passive"))
      (node (ref "IC15") (pin "2") (pinfunction "VDD_2") (pintype "power_in"))
      (node (ref "J1") (pin "2") (pinfunction "2_2") (pintype "bidirectional"))
      (node (ref "J11") (pin "1") (pinfunction "1_1") (pintype "bidirectional"))
      (node (ref "J2") (pin "6") (pinfunction "6_6") (pintype "bidirectional"))
      (node (ref "J9") (pin "2") (pinfunction "2_2") (pintype "bidirectional"))
    )
    (net (code "4") (name "12V") (class "Default")
      (node (ref "C1") (pin "2") (pinfunction "2_2") (pintype "passive"))
      (node (ref "C11") (pin "2") (pinfunction "2_2") (pintype "passive"))
      (node (ref "C12") (pin "2") (pinfunction "2_2") (pintype "passive"))
      (node (ref "C13") (pin "2") (pinfunction "2_2") (pintype "passive"))
      (node (ref "C14") (pin "2") (pinfunction "2_2") (pintype "passive"))
      (node (ref "C2") (pin "2") (pinfunction "2_2") (pintype "passive"))
      (node (ref "C3") (pin "2") (pinfunction "2_2") (pintype "passive"))
      (node (ref "C4") (pin "2") (pinfunction "2_2") (pintype "passive"))
      (node (ref "C5") (pin "2") (pinfunction "2_2") (pintype "passive"))
      (node (ref "C6") (pin "2") (pinfunction "2_2") (pintype "passive"))
      (node (ref "C7") (pin "2") (pinfunction "2_2") (pintype "passive"))
      (node (ref "C8") (pin "2") (pinfunction "2_2") (pintype "passive"))
      (node (ref "IC1") (pin "1") (pinfunction "ENA_1") (pintype "input"))
      (node (ref "IC1") (pin "6") (pinfunction "VDD_6") (pintype "power_in"))
      (node (ref "IC1") (pin "8") (pinfunction "ENB_8") (pintype "input"))
      (node (ref "IC2") (pin "1") (pinfunction "ENA_1") (pintype "input"))
      (node (ref "IC2") (pin "6") (pinfunction "VDD_6") (pintype "power_in"))
      (node (ref "IC2") (pin "8") (pinfunction "ENB_8") (pintype "input"))
      (node (ref "IC3") (pin "1") (pinfunction "ENA_1") (pintype "input"))
      (node (ref "IC3") (pin "6") (pinfunction "VDD_6") (pintype "power_in"))
      (node (ref "IC3") (pin "8") (pinfunction "ENB_8") (pintype "input"))
      (node (ref "IC4") (pin "1") (pinfunction "ENA_1") (pintype "input"))
      (node (ref "IC4") (pin "6") (pinfunction "VDD_6") (pintype "power_in"))
      (node (ref "IC4") (pin "8") (pinfunction "ENB_8") (pintype "input"))
      (node (ref "IC5") (pin "1") (pinfunction "ENA_1") (pintype "input"))
      (node (ref "IC5") (pin "6") (pinfunction "VDD_6") (pintype "power_in"))
      (node (ref "IC5") (pin "8") (pinfunction "ENB_8") (pintype "input"))
      (node (ref "IC6") (pin "1") (pinfunction "ENA_1") (pintype "input"))
      (node (ref "IC6") (pin "6") (pinfunction "VDD_6") (pintype "power_in"))
      (node (ref "IC6") (pin "8") (pinfunction "ENB_8") (pintype "input"))
      (node (ref "J2") (pin "5") (pinfunction "5_5") (pintype "bidirectional"))
    )
    (net (code "5") (name "ACCEL_INTR") (class "Default")
      (node (ref "JP2") (pin "6") (pinfunction "6_6") (pintype "passive"))
      (node (ref "PICO1") (pin "GP22") (pinfunction "GP22_GP22") (pintype "bidirectional"))
    )
    (net (code "6") (name "ADC_INTR") (class "Default")
      (node (ref "JP4") (pin "6") (pinfunction "6_6") (pintype "passive"))
      (node (ref "PICO1") (pin "GP26_A0") (pinfunction "GP26_A0_GP26_A0") (pintype "bidirectional"))
    )
    (net (code "7") (name "BUTTON1") (class "Default")
      (node (ref "IC11") (pin "11") (pinfunction "A_11") (pintype "bidirectional"))
      (node (ref "J8") (pin "1") (pinfunction "1_1") (pintype "bidirectional"))
      (node (ref "R27") (pin "2") (pinfunction "2_2") (pintype "bidirectional"))
    )
    (net (code "8") (name "BUTTON2") (class "Default")
      (node (ref "IC11") (pin "12") (pinfunction "B_12") (pintype "bidirectional"))
      (node (ref "J8") (pin "2") (pinfunction "2_2") (pintype "bidirectional"))
      (node (ref "R27") (pin "3") (pinfunction "3_3") (pintype "bidirectional"))
    )
    (net (code "9") (name "BUTTON3") (class "Default")
      (node (ref "IC11") (pin "13") (pinfunction "C_13") (pintype "bidirectional"))
      (node (ref "J8") (pin "4") (pinfunction "4_4") (pintype "bidirectional"))
      (node (ref "R27") (pin "4") (pinfunction "4_4") (pintype "bidirectional"))
    )
    (net (code "10") (name "BUTTON4") (class "Default")
      (node (ref "IC11") (pin "14") (pinfunction "D_14") (pintype "bidirectional"))
      (node (ref "J8") (pin "5") (pinfunction "5_5") (pintype "bidirectional"))
      (node (ref "R27") (pin "5") (pinfunction "5_5") (pintype "bidirectional"))
    )
    (net (code "11") (name "BUTTON5") (class "Default")
      (node (ref "IC11") (pin "6") (pinfunction "H_6") (pintype "bidirectional"))
      (node (ref "J8") (pin "6") (pinfunction "6_6") (pintype "bidirectional"))
      (node (ref "R27") (pin "6") (pinfunction "6_6") (pintype "bidirectional"))
    )
    (net (code "12") (name "BUTTON6") (class "Default")
      (node (ref "IC11") (pin "5") (pinfunction "G_5") (pintype "bidirectional"))
      (node (ref "J8") (pin "7") (pinfunction "7_7") (pintype "bidirectional"))
      (node (ref "R27") (pin "7") (pinfunction "7_7") (pintype "bidirectional"))
    )
    (net (code "13") (name "BUTTON7") (class "Default")
      (node (ref "IC11") (pin "4") (pinfunction "F_4") (pintype "bidirectional"))
      (node (ref "J8") (pin "8") (pinfunction "8_8") (pintype "bidirectional"))
      (node (ref "R27") (pin "8") (pinfunction "8_8") (pintype "bidirectional"))
    )
    (net (code "14") (name "BUTTON8") (class "Default")
      (node (ref "IC11") (pin "3") (pinfunction "E_3") (pintype "bidirectional"))
      (node (ref "J8") (pin "9") (pinfunction "9_9") (pintype "bidirectional"))
      (node (ref "R27") (pin "9") (pinfunction "9_9") (pintype "bidirectional"))
    )
    (net (code "15") (name "BUTTON9") (class "Default")
      (node (ref "IC12") (pin "11") (pinfunction "A_11") (pintype "bidirectional"))
      (node (ref "J7") (pin "1") (pinfunction "1_1") (pintype "bidirectional"))
      (node (ref "R23") (pin "2") (pinfunction "2_2") (pintype "bidirectional"))
    )
    (net (code "16") (name "BUTTON10") (class "Default")
      (node (ref "IC12") (pin "12") (pinfunction "B_12") (pintype "bidirectional"))
      (node (ref "J7") (pin "2") (pinfunction "2_2") (pintype "bidirectional"))
      (node (ref "R23") (pin "3") (pinfunction "3_3") (pintype "bidirectional"))
    )
    (net (code "17") (name "BUTTON11") (class "Default")
      (node (ref "IC12") (pin "13") (pinfunction "C_13") (pintype "bidirectional"))
      (node (ref "J7") (pin "3") (pinfunction "3_3") (pintype "bidirectional"))
      (node (ref "R23") (pin "4") (pinfunction "4_4") (pintype "bidirectional"))
    )
    (net (code "18") (name "BUTTON12") (class "Default")
      (node (ref "IC12") (pin "14") (pinfunction "D_14") (pintype "bidirectional"))
      (node (ref "J7") (pin "5") (pinfunction "5_5") (pintype "bidirectional"))
      (node (ref "R23") (pin "5") (pinfunction "5_5") (pintype "bidirectional"))
    )
    (net (code "19") (name "BUTTON13") (class "Default")
      (node (ref "IC12") (pin "6") (pinfunction "H_6") (pintype "bidirectional"))
      (node (ref "J7") (pin "6") (pinfunction "6_6") (pintype "bidirectional"))
      (node (ref "R23") (pin "6") (pinfunction "6_6") (pintype "bidirectional"))
    )
    (net (code "20") (name "BUTTON14") (class "Default")
      (node (ref "IC12") (pin "5") (pinfunction "G_5") (pintype "bidirectional"))
      (node (ref "J7") (pin "7") (pinfunction "7_7") (pintype "bidirectional"))
      (node (ref "R23") (pin "7") (pinfunction "7_7") (pintype "bidirectional"))
    )
    (net (code "21") (name "BUTTON15") (class "Default")
      (node (ref "IC12") (pin "4") (pinfunction "F_4") (pintype "bidirectional"))
      (node (ref "J7") (pin "8") (pinfunction "8_8") (pintype "bidirectional"))
      (node (ref "R23") (pin "8") (pinfunction "8_8") (pintype "bidirectional"))
    )
    (net (code "22") (name "BUTTON16") (class "Default")
      (node (ref "IC12") (pin "3") (pinfunction "E_3") (pintype "bidirectional"))
      (node (ref "J7") (pin "9") (pinfunction "9_9") (pintype "bidirectional"))
      (node (ref "R23") (pin "9") (pinfunction "9_9") (pintype "bidirectional"))
    )
    (net (code "23") (name "BUTTON17") (class "Default")
      (node (ref "IC16") (pin "11") (pinfunction "A_11") (pintype "bidirectional"))
      (node (ref "J6") (pin "1") (pinfunction "1_1") (pintype "bidirectional"))
      (node (ref "R24") (pin "2") (pinfunction "2_2") (pintype "bidirectional"))
    )
    (net (code "24") (name "BUTTON18") (class "Default")
      (node (ref "IC16") (pin "12") (pinfunction "B_12") (pintype "bidirectional"))
      (node (ref "J6") (pin "2") (pinfunction "2_2") (pintype "bidirectional"))
      (node (ref "R24") (pin "3") (pinfunction "3_3") (pintype "bidirectional"))
    )
    (net (code "25") (name "BUTTON19") (class "Default")
      (node (ref "IC16") (pin "13") (pinfunction "C_13") (pintype "bidirectional"))
      (node (ref "J6") (pin "3") (pinfunction "3_3") (pintype "bidirectional"))
      (node (ref "R24") (pin "4") (pinfunction "4_4") (pintype "bidirectional"))
    )
    (net (code "26") (name "BUTTON20") (class "Default")
      (node (ref "IC16") (pin "14") (pinfunction "D_14") (pintype "bidirectional"))
      (node (ref "J6") (pin "4") (pinfunction "4_4") (pintype "bidirectional"))
      (node (ref "R24") (pin "5") (pinfunction "5_5") (pintype "bidirectional"))
    )
    (net (code "27") (name "BUTTON21") (class "Default")
      (node (ref "IC16") (pin "6") (pinfunction "H_6") (pintype "bidirectional"))
      (node (ref "J6") (pin "6") (pinfunction "6_6") (pintype "bidirectional"))
      (node (ref "R24") (pin "6") (pinfunction "6_6") (pintype "bidirectional"))
    )
    (net (code "28") (name "BUTTON22") (class "Default")
      (node (ref "IC16") (pin "5") (pinfunction "G_5") (pintype "bidirectional"))
      (node (ref "J6") (pin "7") (pinfunction "7_7") (pintype "bidirectional"))
      (node (ref "R24") (pin "7") (pinfunction "7_7") (pintype "bidirectional"))
    )
    (net (code "29") (name "BUTTON23") (class "Default")
      (node (ref "IC16") (pin "4") (pinfunction "F_4") (pintype "bidirectional"))
      (node (ref "J6") (pin "8") (pinfunction "8_8") (pintype "bidirectional"))
      (node (ref "R24") (pin "8") (pinfunction "8_8") (pintype "bidirectional"))
    )
    (net (code "30") (name "BUTTON24") (class "Default")
      (node (ref "IC16") (pin "3") (pinfunction "E_3") (pintype "bidirectional"))
      (node (ref "J6") (pin "9") (pinfunction "9_9") (pintype "bidirectional"))
      (node (ref "R24") (pin "9") (pinfunction "9_9") (pintype "bidirectional"))
    )
    (net (code "31") (name "BUTTON25") (class "Default")
      (node (ref "IC18") (pin "11") (pinfunction "A_11") (pintype "bidirectional"))
      (node (ref "J5") (pin "1") (pinfunction "1_1") (pintype "bidirectional"))
      (node (ref "R25") (pin "2") (pinfunction "2_2") (pintype "bidirectional"))
    )
    (net (code "32") (name "BUTTON26") (class "Default")
      (node (ref "IC18") (pin "12") (pinfunction "B_12") (pintype "bidirectional"))
      (node (ref "J5") (pin "2") (pinfunction "2_2") (pintype "bidirectional"))
      (node (ref "R25") (pin "3") (pinfunction "3_3") (pintype "bidirectional"))
    )
    (net (code "33") (name "BUTTON27") (class "Default")
      (node (ref "IC18") (pin "13") (pinfunction "C_13") (pintype "bidirectional"))
      (node (ref "J5") (pin "3") (pinfunction "3_3") (pintype "bidirectional"))
      (node (ref "R25") (pin "4") (pinfunction "4_4") (pintype "bidirectional"))
    )
    (net (code "34") (name "BUTTON28") (class "Default")
      (node (ref "IC18") (pin "14") (pinfunction "D_14") (pintype "bidirectional"))
      (node (ref "J5") (pin "4") (pinfunction "4_4") (pintype "bidirectional"))
      (node (ref "R25") (pin "5") (pinfunction "5_5") (pintype "bidirectional"))
    )
    (net (code "35") (name "BUTTON29") (class "Default")
      (node (ref "IC18") (pin "6") (pinfunction "H_6") (pintype "bidirectional"))
      (node (ref "J5") (pin "5") (pinfunction "5_5") (pintype "bidirectional"))
      (node (ref "R25") (pin "6") (pinfunction "6_6") (pintype "bidirectional"))
    )
    (net (code "36") (name "BUTTON30") (class "Default")
      (node (ref "IC18") (pin "5") (pinfunction "G_5") (pintype "bidirectional"))
      (node (ref "J5") (pin "7") (pinfunction "7_7") (pintype "bidirectional"))
      (node (ref "R25") (pin "7") (pinfunction "7_7") (pintype "bidirectional"))
    )
    (net (code "37") (name "BUTTON31") (class "Default")
      (node (ref "IC18") (pin "4") (pinfunction "F_4") (pintype "bidirectional"))
      (node (ref "J5") (pin "8") (pinfunction "8_8") (pintype "bidirectional"))
      (node (ref "R25") (pin "8") (pinfunction "8_8") (pintype "bidirectional"))
    )
    (net (code "38") (name "BUTTON32") (class "Default")
      (node (ref "IC18") (pin "3") (pinfunction "E_3") (pintype "bidirectional"))
      (node (ref "J5") (pin "9") (pinfunction "9_9") (pintype "bidirectional"))
      (node (ref "R25") (pin "9") (pinfunction "9_9") (pintype "bidirectional"))
    )
    (net (code "39") (name "BUTTON_CLK") (class "Default")
      (node (ref "IC11") (pin "2") (pinfunction "CLK_2") (pintype "bidirectional"))
      (node (ref "IC12") (pin "2") (pinfunction "CLK_2") (pintype "bidirectional"))
      (node (ref "IC16") (pin "2") (pinfunction "CLK_2") (pintype "bidirectional"))
      (node (ref "IC18") (pin "2") (pinfunction "CLK_2") (pintype "bidirectional"))
      (node (ref "PICO1") (pin "GP19") (pinfunction "GP19_GP19") (pintype "bidirectional"))
    )
    (net (code "40") (name "BUTTON_DATA") (class "Default")
      (node (ref "IC11") (pin "9") (pinfunction "QH_9") (pintype "bidirectional"))
      (node (ref "PICO1") (pin "GP18") (pinfunction "GP18_GP18") (pintype "bidirectional"))
    )
    (net (code "41") (name "BUTTON_SHLD") (class "Default")
      (node (ref "IC11") (pin "1") (pinfunction "SH/~{LD}_1") (pintype "bidirectional"))
      (node (ref "IC12") (pin "1") (pinfunction "SH/~{LD}_1") (pintype "bidirectional"))
      (node (ref "IC16") (pin "1") (pinfunction "SH/~{LD}_1") (pintype "bidirectional"))
      (node (ref "IC18") (pin "1") (pinfunction "SH/~{LD}_1") (pintype "bidirectional"))
      (node (ref "PICO1") (pin "GP20") (pinfunction "GP20_GP20") (pintype "bidirectional"))
    )
    (net (code "42") (name "FLASHCTL1") (class "Default")
      (node (ref "IC7") (pin "1") (pinfunction "I1_1") (pintype "input"))
      (node (ref "IC7") (pin "2") (pinfunction "I2_2") (pintype "input"))
      (node (ref "PICO2") (pin "GP3") (pinfunction "GP3_GP3") (pintype "bidirectional"))
    )
    (net (code "43") (name "FLASHCTL2") (class "Default")
      (node (ref "IC7") (pin "3") (pinfunction "I3_3") (pintype "input"))
      (node (ref "IC7") (pin "4") (pinfunction "I4_4") (pintype "input"))
      (node (ref "PICO2") (pin "GP2") (pinfunction "GP2_GP2") (pintype "bidirectional"))
    )
    (net (code "44") (name "FLASHCTL3") (class "Default")
      (node (ref "IC7") (pin "5") (pinfunction "I5_5") (pintype "input"))
      (node (ref "IC7") (pin "6") (pinfunction "I6_6") (pintype "input"))
      (node (ref "PICO2") (pin "GP1") (pinfunction "GP1_GP1") (pintype "bidirectional"))
    )
    (net (code "45") (name "FLASHCTL4") (class "Default")
      (node (ref "IC7") (pin "7") (pinfunction "I7_7") (pintype "input"))
      (node (ref "IC7") (pin "8") (pinfunction "I8_8") (pintype "input"))
      (node (ref "PICO2") (pin "GP0") (pinfunction "GP0_GP0") (pintype "bidirectional"))
    )
    (net (code "46") (name "FLASHCTL5") (class "Default")
      (node (ref "IC8") (pin "1") (pinfunction "I1_1") (pintype "input"))
      (node (ref "IC8") (pin "2") (pinfunction "I2_2") (pintype "input"))
      (node (ref "PICO2") (pin "GP4") (pinfunction "GP4_GP4") (pintype "bidirectional"))
    )
    (net (code "47") (name "FLASHCTL6") (class "Default")
      (node (ref "IC8") (pin "3") (pinfunction "I3_3") (pintype "input"))
      (node (ref "IC8") (pin "4") (pinfunction "I4_4") (pintype "input"))
      (node (ref "PICO2") (pin "GP5") (pinfunction "GP5_GP5") (pintype "bidirectional"))
    )
    (net (code "48") (name "FLASHCTL7") (class "Default")
      (node (ref "IC8") (pin "5") (pinfunction "I5_5") (pintype "input"))
      (node (ref "IC8") (pin "6") (pinfunction "I6_6") (pintype "input"))
      (node (ref "PICO2") (pin "GP6") (pinfunction "GP6_GP6") (pintype "bidirectional"))
    )
    (net (code "49") (name "FLASHCTL8") (class "Default")
      (node (ref "IC8") (pin "7") (pinfunction "I7_7") (pintype "input"))
      (node (ref "IC8") (pin "8") (pinfunction "I8_8") (pintype "input"))
      (node (ref "PICO2") (pin "GP7") (pinfunction "GP7_GP7") (pintype "bidirectional"))
    )
    (net (code "50") (name "FLASHCTL9") (class "Default")
      (node (ref "IC10") (pin "7") (pinfunction "I7_7") (pintype "input"))
      (node (ref "IC10") (pin "8") (pinfunction "I8_8") (pintype "input"))
      (node (ref "PICO2") (pin "GP8") (pinfunction "GP8_GP8") (pintype "bidirectional"))
    )
    (net (code "51") (name "FLASHCTL10") (class "Default")
      (node (ref "IC10") (pin "5") (pinfunction "I5_5") (pintype "input"))
      (node (ref "IC10") (pin "6") (pinfunction "I6_6") (pintype "input"))
      (node (ref "PICO2") (pin "GP9") (pinfunction "GP9_GP9") (pintype "bidirectional"))
    )
    (net (code "52") (name "FLASHCTL11") (class "Default")
      (node (ref "IC10") (pin "3") (pinfunction "I3_3") (pintype "input"))
      (node (ref "IC10") (pin "4") (pinfunction "I4_4") (pintype "input"))
      (node (ref "PICO2") (pin "GP10") (pinfunction "GP10_GP10") (pintype "bidirectional"))
    )
    (net (code "53") (name "FLASHCTL12") (class "Default")
      (node (ref "IC10") (pin "1") (pinfunction "I1_1") (pintype "input"))
      (node (ref "IC10") (pin "2") (pinfunction "I2_2") (pintype "input"))
      (node (ref "PICO2") (pin "GP11") (pinfunction "GP11_GP11") (pintype "bidirectional"))
    )
    (net (code "54") (name "FLASHCTL13") (class "Default")
      (node (ref "IC9") (pin "5") (pinfunction "I5_5") (pintype "input"))
      (node (ref "IC9") (pin "6") (pinfunction "I6_6") (pintype "input"))
      (node (ref "PICO2") (pin "GP14") (pinfunction "GP14_GP14") (pintype "bidirectional"))
    )
    (net (code "55") (name "FLASHCTL14") (class "Default")
      (node (ref "IC9") (pin "3") (pinfunction "I3_3") (pintype "input"))
      (node (ref "IC9") (pin "4") (pinfunction "I4_4") (pintype "input"))
      (node (ref "PICO2") (pin "GP13") (pinfunction "GP13_GP13") (pintype "bidirectional"))
    )
    (net (code "56") (name "FLASHCTL15") (class "Default")
      (node (ref "IC9") (pin "1") (pinfunction "I1_1") (pintype "input"))
      (node (ref "IC9") (pin "2") (pinfunction "I2_2") (pintype "input"))
      (node (ref "PICO2") (pin "GP12") (pinfunction "GP12_GP12") (pintype "bidirectional"))
    )
    (net (code "57") (name "FLASHCTL16") (class "Default")
      (node (ref "IC9") (pin "7") (pinfunction "I7_7") (pintype "input"))
      (node (ref "IC9") (pin "8") (pinfunction "I8_8") (pintype "input"))
      (node (ref "PICO2") (pin "GP15") (pinfunction "GP15_GP15") (pintype "bidirectional"))
    )
    (net (code "58") (name "FLASHER1") (class "Default")
      (node (ref "IC7") (pin "17") (pinfunction "O2_17") (pintype "open_collector"))
      (node (ref "IC7") (pin "18") (pinfunction "O1_18") (pintype "open_collector"))
      (node (ref "J1") (pin "15") (pinfunction "15_15") (pintype "bidirectional"))
    )
    (net (code "59") (name "FLASHER2") (class "Default")
      (node (ref "IC7") (pin "15") (pinfunction "O4_15") (pintype "open_collector"))
      (node (ref "IC7") (pin "16") (pinfunction "O3_16") (pintype "open_collector"))
      (node (ref "J1") (pin "13") (pinfunction "13_13") (pintype "bidirectional"))
    )
    (net (code "60") (name "FLASHER3") (class "Default")
      (node (ref "IC7") (pin "13") (pinfunction "O6_13") (pintype "open_collector"))
      (node (ref "IC7") (pin "14") (pinfunction "O5_14") (pintype "open_collector"))
      (node (ref "J1") (pin "11") (pinfunction "11_11") (pintype "bidirectional"))
    )
    (net (code "61") (name "FLASHER4") (class "Default")
      (node (ref "IC7") (pin "11") (pinfunction "O8_11") (pintype "open_collector"))
      (node (ref "IC7") (pin "12") (pinfunction "O7_12") (pintype "open_collector"))
      (node (ref "J1") (pin "9") (pinfunction "9_9") (pintype "bidirectional"))
    )
    (net (code "62") (name "FLASHER5") (class "Default")
      (node (ref "IC8") (pin "17") (pinfunction "O2_17") (pintype "open_collector"))
      (node (ref "IC8") (pin "18") (pinfunction "O1_18") (pintype "open_collector"))
      (node (ref "J1") (pin "7") (pinfunction "7_7") (pintype "bidirectional"))
    )
    (net (code "63") (name "FLASHER6") (class "Default")
      (node (ref "IC8") (pin "15") (pinfunction "O4_15") (pintype "open_collector"))
      (node (ref "IC8") (pin "16") (pinfunction "O3_16") (pintype "open_collector"))
      (node (ref "J1") (pin "5") (pinfunction "5_5") (pintype "bidirectional"))
    )
    (net (code "64") (name "FLASHER7") (class "Default")
      (node (ref "IC8") (pin "13") (pinfunction "O6_13") (pintype "open_collector"))
      (node (ref "IC8") (pin "14") (pinfunction "O5_14") (pintype "open_collector"))
      (node (ref "J1") (pin "3") (pinfunction "3_3") (pintype "bidirectional"))
    )
    (net (code "65") (name "FLASHER8") (class "Default")
      (node (ref "IC8") (pin "11") (pinfunction "O8_11") (pintype "open_collector"))
      (node (ref "IC8") (pin "12") (pinfunction "O7_12") (pintype "open_collector"))
      (node (ref "J1") (pin "1") (pinfunction "1_1") (pintype "bidirectional"))
    )
    (net (code "66") (name "FLASHER9") (class "Default")
      (node (ref "IC10") (pin "11") (pinfunction "O8_11") (pintype "open_collector"))
      (node (ref "IC10") (pin "12") (pinfunction "O7_12") (pintype "open_collector"))
      (node (ref "J1") (pin "16") (pinfunction "16_16") (pintype "bidirectional"))
    )
    (net (code "67") (name "FLASHER10") (class "Default")
      (node (ref "IC10") (pin "13") (pinfunction "O6_13") (pintype "open_collector"))
      (node (ref "IC10") (pin "14") (pinfunction "O5_14") (pintype "open_collector"))
      (node (ref "J1") (pin "14") (pinfunction "14_14") (pintype "bidirectional"))
    )
    (net (code "68") (name "FLASHER11") (class "Default")
      (node (ref "IC10") (pin "15") (pinfunction "O4_15") (pintype "open_collector"))
      (node (ref "IC10") (pin "16") (pinfunction "O3_16") (pintype "open_collector"))
      (node (ref "J1") (pin "12") (pinfunction "12_12") (pintype "bidirectional"))
    )
    (net (code "69") (name "FLASHER12") (class "Default")
      (node (ref "IC10") (pin "17") (pinfunction "O2_17") (pintype "open_collector"))
      (node (ref "IC10") (pin "18") (pinfunction "O1_18") (pintype "open_collector"))
      (node (ref "J1") (pin "10") (pinfunction "10_10") (pintype "bidirectional"))
    )
    (net (code "70") (name "FLASHER13") (class "Default")
      (node (ref "IC9") (pin "13") (pinfunction "O6_13") (pintype "open_collector"))
      (node (ref "IC9") (pin "14") (pinfunction "O5_14") (pintype "open_collector"))
      (node (ref "J1") (pin "8") (pinfunction "8_8") (pintype "bidirectional"))
    )
    (net (code "71") (name "FLASHER14") (class "Default")
      (node (ref "IC9") (pin "15") (pinfunction "O4_15") (pintype "open_collector"))
      (node (ref "IC9") (pin "16") (pinfunction "O3_16") (pintype "open_collector"))
      (node (ref "J1") (pin "6") (pinfunction "6_6") (pintype "bidirectional"))
    )
    (net (code "72") (name "FLASHER15") (class "Default")
      (node (ref "IC9") (pin "17") (pinfunction "O2_17") (pintype "open_collector"))
      (node (ref "IC9") (pin "18") (pinfunction "O1_18") (pintype "open_collector"))
      (node (ref "J1") (pin "4") (pinfunction "4_4") (pintype "bidirectional"))
    )
    (net (code "73") (name "FLASHER16") (class "Default")
      (node (ref "IC9") (pin "11") (pinfunction "O8_11") (pintype "open_collector"))
      (node (ref "IC9") (pin "12") (pinfunction "O7_12") (pintype "open_collector"))
      (node (ref "J13") (pin "1") (pinfunction "1_1") (pintype "bidirectional"))
    )
    (net (code "74") (name "GND") (class "Default")
      (node (ref "C1") (pin "1") (pinfunction "1_1") (pintype "passive"))
      (node (ref "C10") (pin "1") (pinfunction "1_1") (pintype "passive"))
      (node (ref "C11") (pin "1") (pinfunction "1_1") (pintype "passive"))
      (node (ref "C12") (pin "1") (pinfunction "1_1") (pintype "passive"))
      (node (ref "C13") (pin "1") (pinfunction "1_1") (pintype "passive"))
      (node (ref "C14") (pin "1") (pinfunction "1_1") (pintype "passive"))
      (node (ref "C15") (pin "2") (pinfunction "2_2") (pintype "passive"))
      (node (ref "C16") (pin "2") (pinfunction "2_2") (pintype "passive"))
      (node (ref "C18") (pin "1") (pinfunction "1_1") (pintype "passive"))
      (node (ref "C19") (pin "1") (pinfunction "1_1") (pintype "passive"))
      (node (ref "C2") (pin "1") (pinfunction "1_1") (pintype "passive"))
      (node (ref "C3") (pin "1") (pinfunction "1_1") (pintype "passive"))
      (node (ref "C4") (pin "1") (pinfunction "1_1") (pintype "passive"))
      (node (ref "C5") (pin "1") (pinfunction "1_1") (pintype "passive"))
      (node (ref "C6") (pin "1") (pinfunction "1_1") (pintype "passive"))
      (node (ref "C7") (pin "1") (pinfunction "1_1") (pintype "passive"))
      (node (ref "C8") (pin "1") (pinfunction "1_1") (pintype "passive"))
      (node (ref "C9") (pin "1") (pinfunction "1_1") (pintype "passive"))
      (node (ref "D4") (pin "C") (pinfunction "C_C") (pintype "passive"))
      (node (ref "IC1") (pin "3") (pinfunction "GND_3") (pintype "power_in"))
      (node (ref "IC10") (pin "9") (pinfunction "GND_9") (pintype "power_in"))
      (node (ref "IC11") (pin "15") (pinfunction "CLK_INH_15") (pintype "bidirectional"))
      (node (ref "IC11") (pin "8") (pinfunction "GND_8") (pintype "bidirectional"))
      (node (ref "IC12") (pin "15") (pinfunction "CLK_INH_15") (pintype "bidirectional"))
      (node (ref "IC12") (pin "8") (pinfunction "GND_8") (pintype "bidirectional"))
      (node (ref "IC13") (pin "7") (pinfunction "GND_7") (pintype "bidirectional"))
      (node (ref "IC15") (pin "3") (pinfunction "GND_3") (pintype "power_in"))
      (node (ref "IC16") (pin "15") (pinfunction "CLK_INH_15") (pintype "bidirectional"))
      (node (ref "IC16") (pin "8") (pinfunction "GND_8") (pintype "bidirectional"))
      (node (ref "IC18") (pin "15") (pinfunction "CLK_INH_15") (pintype "bidirectional"))
      (node (ref "IC18") (pin "8") (pinfunction "GND_8") (pintype "bidirectional"))
      (node (ref "IC2") (pin "3") (pinfunction "GND_3") (pintype "power_in"))
      (node (ref "IC3") (pin "3") (pinfunction "GND_3") (pintype "power_in"))
      (node (ref "IC4") (pin "3") (pinfunction "GND_3") (pintype "power_in"))
      (node (ref "IC5") (pin "3") (pinfunction "GND_3") (pintype "power_in"))
      (node (ref "IC6") (pin "3") (pinfunction "GND_3") (pintype "power_in"))
      (node (ref "IC7") (pin "9") (pinfunction "GND_9") (pintype "power_in"))
      (node (ref "IC8") (pin "9") (pinfunction "GND_9") (pintype "power_in"))
      (node (ref "IC9") (pin "9") (pinfunction "GND_9") (pintype "power_in"))
      (node (ref "J10") (pin "2") (pinfunction "2_2") (pintype "bidirectional"))
      (node (ref "J10") (pin "4") (pinfunction "4_4") (pintype "bidirectional"))
      (node (ref "J12") (pin "2") (pinfunction "2_2") (pintype "passive"))
      (node (ref "J13") (pin "2") (pinfunction "2_2") (pintype "bidirectional"))
      (node (ref "J14") (pin "2") (pinfunction "2_2") (pintype "bidirectional"))
      (node (ref "J14") (pin "4") (pinfunction "4_4") (pintype "bidirectional"))
      (node (ref "J14") (pin "6") (pinfunction "6_6") (pintype "bidirectional"))
      (node (ref "J14") (pin "8") (pinfunction "8_8") (pintype "bidirectional"))
      (node (ref "J2") (pin "1") (pinfunction "1_1") (pintype "bidirectional"))
      (node (ref "J2") (pin "2") (pinfunction "2_2") (pintype "bidirectional"))
      (node (ref "J2") (pin "3") (pinfunction "3_3") (pintype "bidirectional"))
      (node (ref "J2") (pin "4") (pinfunction "4_4") (pintype "bidirectional"))
      (node (ref "J5") (pin "10") (pinfunction "10_10") (pintype "bidirectional"))
      (node (ref "J6") (pin "10") (pinfunction "10_10") (pintype "bidirectional"))
      (node (ref "J7") (pin "10") (pinfunction "10_10") (pintype "bidirectional"))
      (node (ref "J8") (pin "10") (pinfunction "10_10") (pintype "bidirectional"))
      (node (ref "J9") (pin "3") (pinfunction "3_3") (pintype "bidirectional"))
      (node (ref "JP2") (pin "3") (pinfunction "3_3") (pintype "passive"))
      (node (ref "JP4") (pin "2") (pinfunction "2_2") (pintype "passive"))
      (node (ref "JP4") (pin "5") (pinfunction "5_5") (pintype "passive"))
      (node (ref "PICO1") (pin "AGND") (pinfunction "AGND_AGND") (pintype "bidirectional"))
      (node (ref "PICO1") (pin "GND@1") (pinfunction "GND_GND@1") (pintype "bidirectional"))
      (node (ref "PICO1") (pin "GND@2") (pinfunction "GND_GND@2") (pintype "bidirectional"))
      (node (ref "PICO1") (pin "GND@3") (pinfunction "GND_GND@3") (pintype "bidirectional"))
      (node (ref "PICO1") (pin "GND@4") (pinfunction "GND_GND@4") (pintype "bidirectional"))
      (node (ref "PICO1") (pin "GND@6") (pinfunction "GND_GND@6") (pintype "bidirectional"))
      (node (ref "PICO1") (pin "GND@7") (pinfunction "GND_GND@7") (pintype "bidirectional"))
      (node (ref "PICO1") (pin "GND@8") (pinfunction "GND_GND@8") (pintype "bidirectional"))
      (node (ref "PICO2") (pin "GND@1") (pinfunction "GND_GND@1") (pintype "bidirectional"))
      (node (ref "PICO2") (pin "GND@2") (pinfunction "GND_GND@2") (pintype "bidirectional"))
      (node (ref "PICO2") (pin "GND@3") (pinfunction "GND_GND@3") (pintype "bidirectional"))
      (node (ref "PICO2") (pin "GND@4") (pinfunction "GND_GND@4") (pintype "bidirectional"))
      (node (ref "PICO2") (pin "GND@6") (pinfunction "GND_GND@6") (pintype "bidirectional"))
      (node (ref "PICO2") (pin "GND@7") (pinfunction "GND_GND@7") (pintype "bidirectional"))
      (node (ref "PICO2") (pin "GND@8") (pinfunction "GND_GND@8") (pintype "bidirectional"))
      (node (ref "Q1") (pin "3") (pinfunction "S_3") (pintype "passive"))
      (node (ref "Q10") (pin "3") (pinfunction "S_3") (pintype "passive"))
      (node (ref "Q11") (pin "3") (pinfunction "S_3") (pintype "passive"))
      (node (ref "Q12") (pin "3") (pinfunction "S_3") (pintype "passive"))
      (node (ref "Q16") (pin "1") (pinfunction "E_1") (pintype "bidirectional"))
      (node (ref "Q2") (pin "3") (pinfunction "S_3") (pintype "passive"))
      (node (ref "Q3") (pin "3") (pinfunction "S_3") (pintype "passive"))
      (node (ref "Q4") (pin "3") (pinfunction "S_3") (pintype "passive"))
      (node (ref "Q5") (pin "3") (pinfunction "S_3") (pintype "passive"))
      (node (ref "Q6") (pin "3") (pinfunction "S_3") (pintype "passive"))
      (node (ref "Q7") (pin "3") (pinfunction "S_3") (pintype "passive"))
      (node (ref "Q8") (pin "3") (pinfunction "S_3") (pintype "passive"))
      (node (ref "Q9") (pin "3") (pinfunction "S_3") (pintype "passive"))
      (node (ref "QWIIC1") (pin "1") (pinfunction "GND_1") (pintype "passive"))
      (node (ref "QWIIC1") (pin "MT1") (pinfunction "MT_MT1") (pintype "bidirectional"))
      (node (ref "QWIIC1") (pin "MT2") (pinfunction "MT_MT2") (pintype "bidirectional"))
      (node (ref "R13") (pin "1") (pinfunction "1_1") (pintype "passive"))
      (node (ref "R18") (pin "1") (pinfunction "1_1") (pintype "passive"))
      (node (ref "R20") (pin "2") (pinfunction "2_2") (pintype "passive"))
      (node (ref "R21") (pin "1") (pinfunction "1_1") (pintype "passive"))
      (node (ref "R22") (pin "1") (pinfunction "1_1") (pintype "passive"))
      (node (ref "R31") (pin "1") (pinfunction "1_1") (pintype "passive"))
      (node (ref "S1") (pin "1") (pinfunction "S_1") (pintype "passive"))
      (node (ref "S1") (pin "2") (pinfunction "S1_2") (pintype "passive"))
      (node (ref "S2") (pin "1") (pinfunction "S_1") (pintype "passive"))
      (node (ref "S2") (pin "2") (pinfunction "S1_2") (pintype "passive"))
    )
    (net (code "75") (name "IR_IN") (class "Default")
      (node (ref "J10") (pin "3") (pinfunction "3_3") (pintype "bidirectional"))
      (node (ref "PICO1") (pin "GP4") (pinfunction "GP4_GP4") (pintype "bidirectional"))
    )
    (net (code "76") (name "IR_LED_CATHODE") (class "Default")
      (node (ref "J11") (pin "2") (pinfunction "2_2") (pintype "bidirectional"))
      (node (ref "Q13") (pin "1") (pinfunction "C_1") (pintype "bidirectional"))
    )
    (net (code "77") (name "IR_OUT") (class "Default")
      (node (ref "PICO1") (pin "GP0") (pinfunction "GP0_GP0") (pintype "bidirectional"))
      (node (ref "R19") (pin "1") (pinfunction "1_1") (pintype "passive"))
    )
    (net (code "78") (name "LED_B") (class "Default")
      (node (ref "PICO1") (pin "GP2") (pinfunction "GP2_GP2") (pintype "bidirectional"))
      (node (ref "R10") (pin "1") (pinfunction "1_1") (pintype "passive"))
    )
    (net (code "79") (name "LED_G") (class "Default")
      (node (ref "PICO1") (pin "GP1") (pinfunction "GP1_GP1") (pintype "bidirectional"))
      (node (ref "R11") (pin "1") (pinfunction "1_1") (pintype "passive"))
    )
    (net (code "80") (name "LED_R") (class "Default")
      (node (ref "PICO1") (pin "GP3") (pinfunction "GP3_GP3") (pintype "bidirectional"))
      (node (ref "R9") (pin "1") (pinfunction "1_1") (pintype "passive"))
    )
    (net (code "81") (name "Net-(D1-K)") (class "Default")
      (node (ref "D1") (pin "1") (pinfunction "K_1") (pintype "bidirectional"))
      (node (ref "PICO2") (pin "VSYS") (pinfunction "VSYS_VSYS") (pintype "bidirectional"))
    )
    (net (code "82") (name "Net-(D3-PadC)") (class "Default")
      (node (ref "D3") (pin "C") (pinfunction "C_C") (pintype "passive"))
      (node (ref "D4") (pin "A") (pinfunction "A_A") (pintype "passive"))
    )
    (net (code "83") (name "Net-(IC1-OUTA)") (class "Default")
      (node (ref "IC1") (pin "7") (pinfunction "OUTA_7") (pintype "output"))
      (node (ref "R1") (pin "1") (pinfunction "1_1") (pintype "passive"))
    )
    (net (code "84") (name "Net-(IC1-OUTB)") (class "Default")
      (node (ref "IC1") (pin "5") (pinfunction "OUTB_5") (pintype "output"))
      (node (ref "R2") (pin "1") (pinfunction "1_1") (pintype "passive"))
    )
    (net (code "85") (name "Net-(IC2-OUTA)") (class "Default")
      (node (ref "IC2") (pin "7") (pinfunction "OUTA_7") (pintype "output"))
      (node (ref "R3") (pin "1") (pinfunction "1_1") (pintype "passive"))
    )
    (net (code "86") (name "Net-(IC2-OUTB)") (class "Default")
      (node (ref "IC2") (pin "5") (pinfunction "OUTB_5") (pintype "output"))
      (node (ref "R4") (pin "1") (pinfunction "1_1") (pintype "passive"))
    )
    (net (code "87") (name "Net-(IC3-OUTA)") (class "Default")
      (node (ref "IC3") (pin "7") (pinfunction "OUTA_7") (pintype "output"))
      (node (ref "R5") (pin "1") (pinfunction "1_1") (pintype "passive"))
    )
    (net (code "88") (name "Net-(IC3-OUTB)") (class "Default")
      (node (ref "IC3") (pin "5") (pinfunction "OUTB_5") (pintype "output"))
      (node (ref "R6") (pin "1") (pinfunction "1_1") (pintype "passive"))
    )
    (net (code "89") (name "Net-(IC4-OUTA)") (class "Default")
      (node (ref "IC4") (pin "7") (pinfunction "OUTA_7") (pintype "output"))
      (node (ref "R7") (pin "1") (pinfunction "1_1") (pintype "passive"))
    )
    (net (code "90") (name "Net-(IC4-OUTB)") (class "Default")
      (node (ref "IC4") (pin "5") (pinfunction "OUTB_5") (pintype "output"))
      (node (ref "R8") (pin "1") (pinfunction "1_1") (pintype "passive"))
    )
    (net (code "91") (name "Net-(IC5-OUTA)") (class "Default")
      (node (ref "IC5") (pin "7") (pinfunction "OUTA_7") (pintype "output"))
      (node (ref "R14") (pin "1") (pinfunction "1_1") (pintype "passive"))
    )
    (net (code "92") (name "Net-(IC5-OUTB)") (class "Default")
      (node (ref "IC5") (pin "5") (pinfunction "OUTB_5") (pintype "output"))
      (node (ref "R15") (pin "1") (pinfunction "1_1") (pintype "passive"))
    )
    (net (code "93") (name "Net-(IC6-OUTA)") (class "Default")
      (node (ref "IC6") (pin "7") (pinfunction "OUTA_7") (pintype "output"))
      (node (ref "R16") (pin "1") (pinfunction "1_1") (pintype "passive"))
    )
    (net (code "94") (name "Net-(IC6-OUTB)") (class "Default")
      (node (ref "IC6") (pin "5") (pinfunction "OUTB_5") (pintype "output"))
      (node (ref "R17") (pin "1") (pinfunction "1_1") (pintype "passive"))
    )
    (net (code "95") (name "Net-(IC11-SER)") (class "Default")
      (node (ref "IC11") (pin "10") (pinfunction "SER_10") (pintype "bidirectional"))
      (node (ref "IC12") (pin "9") (pinfunction "QH_9") (pintype "bidirectional"))
    )
    (net (code "96") (name "Net-(IC12-SER)") (class "Default")
      (node (ref "IC12") (pin "10") (pinfunction "SER_10") (pintype "bidirectional"))
      (node (ref "IC16") (pin "9") (pinfunction "QH_9") (pintype "bidirectional"))
    )
    (net (code "97") (name "Net-(IC13-1CLK)") (class "Default")
      (node (ref "IC13") (pin "3") (pinfunction "1CLK_3") (pintype "bidirectional"))
      (node (ref "IC14") (pin "7") (pinfunction "EMIT_7") (pintype "passive"))
      (node (ref "R20") (pin "1") (pinfunction "1_1") (pintype "passive"))
    )
    (net (code "98") (name "Net-(IC13-1Q)") (class "Default")
      (node (ref "IC13") (pin "5") (pinfunction "1Q_5") (pintype "bidirectional"))
      (node (ref "IC14") (pin "3") (pinfunction "A_3") (pintype "passive"))
    )
    (net (code "99") (name "Net-(IC13-~{1CLR})") (class "Default")
      (node (ref "IC13") (pin "1") (pinfunction "~{1CLR}_1") (pintype "bidirectional"))
      (node (ref "IC15") (pin "1") (pinfunction "OUT_1") (pintype "output"))
    )
    (net (code "100") (name "Net-(IC14A-C)") (class "Default")
      (node (ref "IC14") (pin "2") (pinfunction "C_2") (pintype "passive"))
      (node (ref "R18") (pin "2") (pinfunction "2_2") (pintype "passive"))
    )
    (net (code "101") (name "Net-(IC14B-C)") (class "Default")
      (node (ref "IC14") (pin "4") (pinfunction "C_4") (pintype "passive"))
      (node (ref "R21") (pin "2") (pinfunction "2_2") (pintype "passive"))
    )
    (net (code "102") (name "Net-(IC16-SER)") (class "Default")
      (node (ref "IC16") (pin "10") (pinfunction "SER_10") (pintype "bidirectional"))
      (node (ref "IC18") (pin "9") (pinfunction "QH_9") (pintype "bidirectional"))
    )
    (net (code "103") (name "Net-(JP3-Pad2)") (class "Default")
      (node (ref "JP3") (pin "2") (pinfunction "2_2") (pintype "passive"))
      (node (ref "R12") (pin "1") (pinfunction "1_1") (pintype "passive"))
      (node (ref "R13") (pin "2") (pinfunction "2_2") (pintype "passive"))
    )
    (net (code "104") (name "Net-(LED2-BLUE_K)") (class "Default")
      (node (ref "LED2") (pin "3") (pinfunction "BLUE_K_3") (pintype "bidirectional"))
      (node (ref "R10") (pin "2") (pinfunction "2_2") (pintype "passive"))
    )
    (net (code "105") (name "Net-(LED2-GREEN_K)") (class "Default")
      (node (ref "LED2") (pin "4") (pinfunction "GREEN_K_4") (pintype "bidirectional"))
      (node (ref "R11") (pin "2") (pinfunction "2_2") (pintype "passive"))
    )
    (net (code "106") (name "Net-(LED2-RED_K)") (class "Default")
      (node (ref "LED2") (pin "1") (pinfunction "RED_K_1") (pintype "bidirectional"))
      (node (ref "R9") (pin "2") (pinfunction "2_2") (pintype "passive"))
    )
    (net (code "107") (name "Net-(PICO2-Pad3V3)") (class "Default")
      (node (ref "PICO2") (pin "3V3") (pinfunction "3V3_3V3") (pintype "bidirectional"))
      (node (ref "R32") (pin "2") (pinfunction "2_2") (pintype "passive"))
    )
    (net (code "108") (name "Net-(Q1-G)") (class "Default")
      (node (ref "Q1") (pin "1") (pinfunction "G_1") (pintype "passive"))
      (node (ref "R1") (pin "2") (pinfunction "2_2") (pintype "passive"))
    )
    (net (code "109") (name "Net-(Q2-G)") (class "Default")
      (node (ref "Q2") (pin "1") (pinfunction "G_1") (pintype "passive"))
      (node (ref "R2") (pin "2") (pinfunction "2_2") (pintype "passive"))
    )
    (net (code "110") (name "Net-(Q3-G)") (class "Default")
      (node (ref "Q3") (pin "1") (pinfunction "G_1") (pintype "passive"))
      (node (ref "R3") (pin "2") (pinfunction "2_2") (pintype "passive"))
    )
    (net (code "111") (name "Net-(Q4-G)") (class "Default")
      (node (ref "Q4") (pin "1") (pinfunction "G_1") (pintype "passive"))
      (node (ref "R4") (pin "2") (pinfunction "2_2") (pintype "passive"))
    )
    (net (code "112") (name "Net-(Q5-G)") (class "Default")
      (node (ref "Q5") (pin "1") (pinfunction "G_1") (pintype "passive"))
      (node (ref "R5") (pin "2") (pinfunction "2_2") (pintype "passive"))
    )
    (net (code "113") (name "Net-(Q6-G)") (class "Default")
      (node (ref "Q6") (pin "1") (pinfunction "G_1") (pintype "passive"))
      (node (ref "R6") (pin "2") (pinfunction "2_2") (pintype "passive"))
    )
    (net (code "114") (name "Net-(Q7-G)") (class "Default")
      (node (ref "Q7") (pin "1") (pinfunction "G_1") (pintype "passive"))
      (node (ref "R7") (pin "2") (pinfunction "2_2") (pintype "passive"))
    )
    (net (code "115") (name "Net-(Q8-G)") (class "Default")
      (node (ref "Q8") (pin "1") (pinfunction "G_1") (pintype "passive"))
      (node (ref "R8") (pin "2") (pinfunction "2_2") (pintype "passive"))
    )
    (net (code "116") (name "Net-(Q9-G)") (class "Default")
      (node (ref "Q9") (pin "1") (pinfunction "G_1") (pintype "passive"))
      (node (ref "R14") (pin "2") (pinfunction "2_2") (pintype "passive"))
    )
    (net (code "117") (name "Net-(Q10-G)") (class "Default")
      (node (ref "Q10") (pin "1") (pinfunction "G_1") (pintype "passive"))
      (node (ref "R15") (pin "2") (pinfunction "2_2") (pintype "passive"))
    )
    (net (code "118") (name "Net-(Q11-G)") (class "Default")
      (node (ref "Q11") (pin "1") (pinfunction "G_1") (pintype "passive"))
      (node (ref "R16") (pin "2") (pinfunction "2_2") (pintype "passive"))
    )
    (net (code "119") (name "Net-(Q12-G)") (class "Default")
      (node (ref "Q12") (pin "1") (pinfunction "G_1") (pintype "passive"))
      (node (ref "R17") (pin "2") (pinfunction "2_2") (pintype "passive"))
    )
    (net (code "120") (name "Net-(Q13-B)") (class "Default")
      (node (ref "D3") (pin "A") (pinfunction "A_A") (pintype "passive"))
      (node (ref "Q13") (pin "2") (pinfunction "B_2") (pintype "bidirectional"))
      (node (ref "R19") (pin "2") (pinfunction "2_2") (pintype "passive"))
    )
    (net (code "121") (name "Net-(Q13-E)") (class "Default")
      (node (ref "Q13") (pin "3") (pinfunction "E_3") (pintype "bidirectional"))
      (node (ref "R31") (pin "2") (pinfunction "2_2") (pintype "passive"))
    )
    (net (code "122") (name "Net-(Q15-B)") (class "Default")
      (node (ref "Q15") (pin "3") (pinfunction "B_3") (pintype "bidirectional"))
      (node (ref "R26") (pin "2") (pinfunction "2_2") (pintype "passive"))
    )
    (net (code "123") (name "Net-(Q16-B)") (class "Default")
      (node (ref "Q16") (pin "2") (pinfunction "B_2") (pintype "bidirectional"))
      (node (ref "R33") (pin "2") (pinfunction "2_2") (pintype "passive"))
    )
    (net (code "124") (name "Net-(Q16-C)") (class "Default")
      (node (ref "PICO2") (pin "RUN") (pinfunction "RUN_RUN") (pintype "bidirectional"))
      (node (ref "Q16") (pin "3") (pinfunction "C_3") (pintype "bidirectional"))
      (node (ref "R32") (pin "1") (pinfunction "1_1") (pintype "passive"))
      (node (ref "S2") (pin "3") (pinfunction "P_3") (pintype "passive"))
      (node (ref "S2") (pin "4") (pinfunction "P1_4") (pintype "passive"))
    )
    (net (code "125") (name "Net-(S1-P)") (class "Default")
      (node (ref "PICO1") (pin "RUN") (pinfunction "RUN_RUN") (pintype "bidirectional"))
      (node (ref "R34") (pin "1") (pinfunction "1_1") (pintype "passive"))
      (node (ref "S1") (pin "3") (pinfunction "P_3") (pintype "passive"))
      (node (ref "S1") (pin "4") (pinfunction "P1_4") (pintype "passive"))
    )
    (net (code "126") (name "OUT1") (class "Default")
      (node (ref "J4") (pin "1") (pinfunction "1_1") (pintype "bidirectional"))
      (node (ref "Q1") (pin "2") (pinfunction "D_2") (pintype "passive"))
    )
    (net (code "127") (name "OUT2") (class "Default")
      (node (ref "J4") (pin "3") (pinfunction "3_3") (pintype "bidirectional"))
      (node (ref "Q2") (pin "2") (pinfunction "D_2") (pintype "passive"))
    )
    (net (code "128") (name "OUT3") (class "Default")
      (node (ref "J4") (pin "4") (pinfunction "4_4") (pintype "bidirectional"))
      (node (ref "Q3") (pin "2") (pinfunction "D_2") (pintype "passive"))
    )
    (net (code "129") (name "OUT4") (class "Default")
      (node (ref "J4") (pin "5") (pinfunction "5_5") (pintype "bidirectional"))
      (node (ref "Q4") (pin "2") (pinfunction "D_2") (pintype "passive"))
    )
    (net (code "130") (name "OUT5") (class "Default")
      (node (ref "J4") (pin "6") (pinfunction "6_6") (pintype "bidirectional"))
      (node (ref "Q5") (pin "2") (pinfunction "D_2") (pintype "passive"))
    )
    (net (code "131") (name "OUT6") (class "Default")
      (node (ref "J4") (pin "7") (pinfunction "7_7") (pintype "bidirectional"))
      (node (ref "Q6") (pin "2") (pinfunction "D_2") (pintype "passive"))
    )
    (net (code "132") (name "OUT7") (class "Default")
      (node (ref "J4") (pin "8") (pinfunction "8_8") (pintype "bidirectional"))
      (node (ref "Q7") (pin "2") (pinfunction "D_2") (pintype "passive"))
    )
    (net (code "133") (name "OUT8") (class "Default")
      (node (ref "J4") (pin "9") (pinfunction "9_9") (pintype "bidirectional"))
      (node (ref "Q8") (pin "2") (pinfunction "D_2") (pintype "passive"))
    )
    (net (code "134") (name "OUT9") (class "Default")
      (node (ref "J3") (pin "1") (pinfunction "1_1") (pintype "bidirectional"))
      (node (ref "Q9") (pin "2") (pinfunction "D_2") (pintype "passive"))
    )
    (net (code "135") (name "OUT10") (class "Default")
      (node (ref "J3") (pin "3") (pinfunction "3_3") (pintype "bidirectional"))
      (node (ref "Q10") (pin "2") (pinfunction "D_2") (pintype "passive"))
    )
    (net (code "136") (name "OUT11") (class "Default")
      (node (ref "J3") (pin "4") (pinfunction "4_4") (pintype "bidirectional"))
      (node (ref "Q11") (pin "2") (pinfunction "D_2") (pintype "passive"))
    )
    (net (code "137") (name "OUT12") (class "Default")
      (node (ref "J3") (pin "5") (pinfunction "5_5") (pintype "bidirectional"))
      (node (ref "Q12") (pin "2") (pinfunction "D_2") (pintype "passive"))
    )
    (net (code "138") (name "OUTCTL1") (class "Default")
      (node (ref "IC1") (pin "2") (pinfunction "INA_2") (pintype "input"))
      (node (ref "PICO1") (pin "GP8") (pinfunction "GP8_GP8") (pintype "bidirectional"))
    )
    (net (code "139") (name "OUTCTL2") (class "Default")
      (node (ref "IC1") (pin "4") (pinfunction "INB_4") (pintype "input"))
      (node (ref "PICO1") (pin "GP9") (pinfunction "GP9_GP9") (pintype "bidirectional"))
    )
    (net (code "140") (name "OUTCTL3") (class "Default")
      (node (ref "IC2") (pin "2") (pinfunction "INA_2") (pintype "input"))
      (node (ref "PICO1") (pin "GP14") (pinfunction "GP14_GP14") (pintype "bidirectional"))
    )
    (net (code "141") (name "OUTCTL4") (class "Default")
      (node (ref "IC2") (pin "4") (pinfunction "INB_4") (pintype "input"))
      (node (ref "PICO1") (pin "GP15") (pinfunction "GP15_GP15") (pintype "bidirectional"))
    )
    (net (code "142") (name "OUTCTL5") (class "Default")
      (node (ref "IC3") (pin "2") (pinfunction "INA_2") (pintype "input"))
      (node (ref "PICO2") (pin "GP16") (pinfunction "GP16_GP16") (pintype "bidirectional"))
    )
    (net (code "143") (name "OUTCTL6") (class "Default")
      (node (ref "IC3") (pin "4") (pinfunction "INB_4") (pintype "input"))
      (node (ref "PICO2") (pin "GP17") (pinfunction "GP17_GP17") (pintype "bidirectional"))
    )
    (net (code "144") (name "OUTCTL7") (class "Default")
      (node (ref "IC4") (pin "2") (pinfunction "INA_2") (pintype "input"))
      (node (ref "PICO2") (pin "GP18") (pinfunction "GP18_GP18") (pintype "bidirectional"))
    )
    (net (code "145") (name "OUTCTL8") (class "Default")
      (node (ref "IC4") (pin "4") (pinfunction "INB_4") (pintype "input"))
      (node (ref "PICO2") (pin "GP19") (pinfunction "GP19_GP19") (pintype "bidirectional"))
    )
    (net (code "146") (name "OUTCTL9") (class "Default")
      (node (ref "IC5") (pin "2") (pinfunction "INA_2") (pintype "input"))
      (node (ref "PICO2") (pin "GP22") (pinfunction "GP22_GP22") (pintype "bidirectional"))
    )
    (net (code "147") (name "OUTCTL10") (class "Default")
      (node (ref "IC5") (pin "4") (pinfunction "INB_4") (pintype "input"))
      (node (ref "PICO2") (pin "GP21") (pinfunction "GP21_GP21") (pintype "bidirectional"))
    )
    (net (code "148") (name "OUTCTL11") (class "Default")
      (node (ref "IC6") (pin "2") (pinfunction "INA_2") (pintype "input"))
      (node (ref "PICO2") (pin "GP20") (pinfunction "GP20_GP20") (pintype "bidirectional"))
    )
    (net (code "149") (name "OUTCTL12") (class "Default")
      (node (ref "IC6") (pin "4") (pinfunction "INB_4") (pintype "input"))
      (node (ref "PICO2") (pin "GP28_A2") (pinfunction "GP28_A2_GP28_A2") (pintype "bidirectional"))
    )
    (net (code "150") (name "PLUNGER_ADC") (class "Default")
      (node (ref "J9") (pin "8") (pinfunction "8_8") (pintype "bidirectional"))
      (node (ref "JP3") (pin "5") (pinfunction "5_5") (pintype "passive"))
      (node (ref "PICO1") (pin "GP28_A2") (pinfunction "GP28_A2_GP28_A2") (pintype "bidirectional"))
    )
    (net (code "151") (name "PLUNGER_IRQ1_SCL") (class "Default")
      (node (ref "J9") (pin "6") (pinfunction "6_6") (pintype "bidirectional"))
      (node (ref "PICO1") (pin "GP13") (pinfunction "GP13_GP13") (pintype "bidirectional"))
    )
    (net (code "152") (name "PLUNGER_IRQ2") (class "Default")
      (node (ref "J9") (pin "5") (pinfunction "5_5") (pintype "bidirectional"))
      (node (ref "PICO1") (pin "GP27_A1") (pinfunction "GP27_A1_GP27_A1") (pintype "bidirectional"))
    )
    (net (code "153") (name "PLUNGER_SDA") (class "Default")
      (node (ref "J9") (pin "1") (pinfunction "1_1") (pintype "bidirectional"))
      (node (ref "PICO1") (pin "GP12") (pinfunction "GP12_GP12") (pintype "bidirectional"))
    )
    (net (code "154") (name "PSU2_STATUS_SENSE") (class "Default")
      (node (ref "IC14") (pin "5") (pinfunction "EMIT_5") (pintype "passive"))
      (node (ref "PICO1") (pin "GP11") (pinfunction "GP11_GP11") (pintype "bidirectional"))
      (node (ref "R22") (pin "2") (pinfunction "2_2") (pintype "passive"))
    )
    (net (code "155") (name "PSU2_STATUS_SET") (class "Default")
      (node (ref "IC14") (pin "1") (pinfunction "A_1") (pintype "passive"))
      (node (ref "PICO1") (pin "GP10") (pinfunction "GP10_GP10") (pintype "bidirectional"))
    )
    (net (code "156") (name "SCL") (class "Default")
      (node (ref "J14") (pin "3") (pinfunction "3_3") (pintype "bidirectional"))
      (node (ref "JP2") (pin "4") (pinfunction "4_4") (pintype "passive"))
      (node (ref "JP4") (pin "3") (pinfunction "3_3") (pintype "passive"))
      (node (ref "PICO1") (pin "GP7") (pinfunction "GP7_GP7") (pintype "bidirectional"))
      (node (ref "PICO2") (pin "GP27_A1") (pinfunction "GP27_A1_GP27_A1") (pintype "bidirectional"))
      (node (ref "QWIIC1") (pin "4") (pinfunction "SCL_4") (pintype "passive"))
      (node (ref "R30") (pin "1") (pinfunction "1_1") (pintype "passive"))
    )
    (net (code "157") (name "SDA") (class "Default")
      (node (ref "J14") (pin "5") (pinfunction "5_5") (pintype "bidirectional"))
      (node (ref "JP2") (pin "5") (pinfunction "5_5") (pintype "passive"))
      (node (ref "JP4") (pin "4") (pinfunction "4_4") (pintype "passive"))
      (node (ref "PICO1") (pin "GP6") (pinfunction "GP6_GP6") (pintype "bidirectional"))
      (node (ref "PICO2") (pin "GP26_A0") (pinfunction "GP26_A0_GP26_A0") (pintype "bidirectional"))
      (node (ref "QWIIC1") (pin "3") (pinfunction "SDA_3") (pintype "passive"))
      (node (ref "R29") (pin "1") (pinfunction "1_1") (pintype "passive"))
    )
    (net (code "158") (name "UART0_RX") (class "Default")
      (node (ref "J12") (pin "3") (pinfunction "3_3") (pintype "passive"))
      (node (ref "PICO1") (pin "GP17") (pinfunction "GP17_GP17") (pintype "bidirectional"))
    )
    (net (code "159") (name "UART0_TX") (class "Default")
      (node (ref "J12") (pin "1") (pinfunction "1_1") (pintype "passive"))
      (node (ref "PICO1") (pin "GP16") (pinfunction "GP16_GP16") (pintype "bidirectional"))
    )
    (net (code "160") (name "VBUS") (class "Default")
      (node (ref "D1") (pin "2") (pinfunction "A_2") (pintype "bidirectional"))
      (node (ref "J14") (pin "1") (pinfunction "1_1") (pintype "bidirectional"))
      (node (ref "PICO1") (pin "VBUS") (pinfunction "VBUS_VBUS") (pintype "bidirectional"))
    )
    (net (code "161") (name "unconnected-(IC7-CD+-Pad10)") (class "Default")
      (node (ref "IC7") (pin "10") (pinfunction "CD+_10") (pintype "passive"))
    )
    (net (code "162") (name "unconnected-(IC8-CD+-Pad10)") (class "Default")
      (node (ref "IC8") (pin "10") (pinfunction "CD+_10") (pintype "passive"))
    )
    (net (code "163") (name "unconnected-(IC9-CD+-Pad10)") (class "Default")
      (node (ref "IC9") (pin "10") (pinfunction "CD+_10") (pintype "passive"))
    )
    (net (code "164") (name "unconnected-(IC10-CD+-Pad10)") (class "Default")
      (node (ref "IC10") (pin "10") (pinfunction "CD+_10") (pintype "passive"))
    )
    (net (code "165") (name "unconnected-(IC11-~{QH}-Pad7)") (class "Default")
      (node (ref "IC11") (pin "7") (pinfunction "~{QH}_7") (pintype "bidirectional"))
    )
    (net (code "166") (name "unconnected-(IC12-~{QH}-Pad7)") (class "Default")
      (node (ref "IC12") (pin "7") (pinfunction "~{QH}_7") (pintype "bidirectional"))
    )
    (net (code "167") (name "unconnected-(IC13-1~{Q}-Pad6)") (class "Default")
      (node (ref "IC13") (pin "6") (pinfunction "1~{Q}_6") (pintype "bidirectional"))
    )
    (net (code "168") (name "unconnected-(IC13-2CLK-Pad11)") (class "Default")
      (node (ref "IC13") (pin "11") (pinfunction "2CLK_11") (pintype "bidirectional"))
    )
    (net (code "169") (name "unconnected-(IC13-2D-Pad12)") (class "Default")
      (node (ref "IC13") (pin "12") (pinfunction "2D_12") (pintype "bidirectional"))
    )
    (net (code "170") (name "unconnected-(IC13-2Q-Pad9)") (class "Default")
      (node (ref "IC13") (pin "9") (pinfunction "2Q_9") (pintype "bidirectional"))
    )
    (net (code "171") (name "unconnected-(IC13-2~{CLR}-Pad13)") (class "Default")
      (node (ref "IC13") (pin "13") (pinfunction "2~{CLR}_13") (pintype "bidirectional"))
    )
    (net (code "172") (name "unconnected-(IC13-2~{PRE}-Pad10)") (class "Default")
      (node (ref "IC13") (pin "10") (pinfunction "2~{PRE}_10") (pintype "bidirectional"))
    )
    (net (code "173") (name "unconnected-(IC13-2~{Q}-Pad8)") (class "Default")
      (node (ref "IC13") (pin "8") (pinfunction "2~{Q}_8") (pintype "bidirectional"))
    )
    (net (code "174") (name "unconnected-(IC16-~{QH}-Pad7)") (class "Default")
      (node (ref "IC16") (pin "7") (pinfunction "~{QH}_7") (pintype "bidirectional"))
    )
    (net (code "175") (name "unconnected-(IC18-SER-Pad10)") (class "Default")
      (node (ref "IC18") (pin "10") (pinfunction "SER_10") (pintype "bidirectional"))
    )
    (net (code "176") (name "unconnected-(IC18-~{QH}-Pad7)") (class "Default")
      (node (ref "IC18") (pin "7") (pinfunction "~{QH}_7") (pintype "bidirectional"))
    )
    (net (code "177") (name "unconnected-(J3-Pad2)") (class "Default")
      (node (ref "J3") (pin "2") (pinfunction "2_2") (pintype "bidirectional"))
    )
    (net (code "178") (name "unconnected-(J4-Pad2)") (class "Default")
      (node (ref "J4") (pin "2") (pinfunction "2_2") (pintype "bidirectional"))
    )
    (net (code "179") (name "unconnected-(J5-Pad6)") (class "Default")
      (node (ref "J5") (pin "6") (pinfunction "6_6") (pintype "bidirectional"))
    )
    (net (code "180") (name "unconnected-(J6-Pad5)") (class "Default")
      (node (ref "J6") (pin "5") (pinfunction "5_5") (pintype "bidirectional"))
    )
    (net (code "181") (name "unconnected-(J7-Pad4)") (class "Default")
      (node (ref "J7") (pin "4") (pinfunction "4_4") (pintype "bidirectional"))
    )
    (net (code "182") (name "unconnected-(J8-Pad3)") (class "Default")
      (node (ref "J8") (pin "3") (pinfunction "3_3") (pintype "bidirectional"))
    )
    (net (code "183") (name "unconnected-(J9-Pad7)") (class "Default")
      (node (ref "J9") (pin "7") (pinfunction "7_7") (pintype "bidirectional"))
    )
    (net (code "184") (name "unconnected-(JP1-Pad1)") (class "Default")
      (node (ref "JP1") (pin "1") (pinfunction "1_1") (pintype "passive"))
    )
    (net (code "185") (name "unconnected-(JP1-Pad2)") (class "Default")
      (node (ref "JP1") (pin "2") (pinfunction "2_2") (pintype "passive"))
    )
    (net (code "186") (name "unconnected-(JP1-Pad3)") (class "Default")
      (node (ref "JP1") (pin "3") (pinfunction "3_3") (pintype "passive"))
    )
    (net (code "187") (name "unconnected-(JP1-Pad4)") (class "Default")
      (node (ref "JP1") (pin "4") (pinfunction "4_4") (pintype "passive"))
    )
    (net (code "188") (name "unconnected-(JP1-Pad5)") (class "Default")
      (node (ref "JP1") (pin "5") (pinfunction "5_5") (pintype "passive"))
    )
    (net (code "189") (name "unconnected-(JP2-Pad2)") (class "Default")
      (node (ref "JP2") (pin "2") (pinfunction "2_2") (pintype "passive"))
    )
    (net (code "190") (name "unconnected-(JP3-Pad1)") (class "Default")
      (node (ref "JP3") (pin "1") (pinfunction "1_1") (pintype "passive"))
    )
    (net (code "191") (name "unconnected-(JP3-Pad3)") (class "Default")
      (node (ref "JP3") (pin "3") (pinfunction "3_3") (pintype "passive"))
    )
    (net (code "192") (name "unconnected-(JP3-Pad4)") (class "Default")
      (node (ref "JP3") (pin "4") (pinfunction "4_4") (pintype "passive"))
    )
    (net (code "193") (name "unconnected-(JP3-Pad6)") (class "Default")
      (node (ref "JP3") (pin "6") (pinfunction "6_6") (pintype "passive"))
    )
    (net (code "194") (name "unconnected-(PICO1-Pad3V3_EN)") (class "Default")
      (node (ref "PICO1") (pin "3V3_EN") (pinfunction "3V3_EN_3V3_EN") (pintype "bidirectional"))
    )
    (net (code "195") (name "unconnected-(PICO1-PadADC_VREF)") (class "Default")
      (node (ref "PICO1") (pin "ADC_VREF") (pinfunction "ADC_VREF_ADC_VREF") (pintype "bidirectional"))
    )
    (net (code "196") (name "unconnected-(PICO1-PadGP21)") (class "Default")
      (node (ref "PICO1") (pin "GP21") (pinfunction "GP21_GP21") (pintype "bidirectional"))
    )
    (net (code "197") (name "unconnected-(PICO1-PadVSYS)") (class "Default")
      (node (ref "PICO1") (pin "VSYS") (pinfunction "VSYS_VSYS") (pintype "bidirectional"))
    )
    (net (code "198") (name "unconnected-(PICO2-Pad3V3_EN)") (class "Default")
      (node (ref "PICO2") (pin "3V3_EN") (pinfunction "3V3_EN_3V3_EN") (pintype "bidirectional"))
    )
    (net (code "199") (name "unconnected-(PICO2-PadADC_VREF)") (class "Default")
      (node (ref "PICO2") (pin "ADC_VREF") (pinfunction "ADC_VREF_ADC_VREF") (pintype "bidirectional"))
    )
    (net (code "200") (name "unconnected-(PICO2-PadAGND)") (class "Default")
      (node (ref "PICO2") (pin "AGND") (pinfunction "AGND_AGND") (pintype "bidirectional"))
    )
    (net (code "201") (name "unconnected-(PICO2-PadVBUS)") (class "Default")
      (node (ref "PICO2") (pin "VBUS") (pinfunction "VBUS_VBUS") (pintype "bidirectional"))
    )
    (net (code "202") (name "{slash}PERIPHERAL_POWER_ENABLE") (class "Default")
      (node (ref "J14") (pin "7") (pinfunction "7_7") (pintype "bidirectional"))
      (node (ref "PICO1") (pin "GP5") (pinfunction "GP5_GP5") (pintype "bidirectional"))
      (node (ref "R26") (pin "1") (pinfunction "1_1") (pintype "passive"))
      (node (ref "R28") (pin "1") (pinfunction "1_1") (pintype "passive"))
      (node (ref "R33") (pin "1") (pinfunction "1_1") (pintype "passive"))
    )
  )
)
